# USB3_0_to_SATA.net
KiCad netlist of a schematic drawn in EAGLE
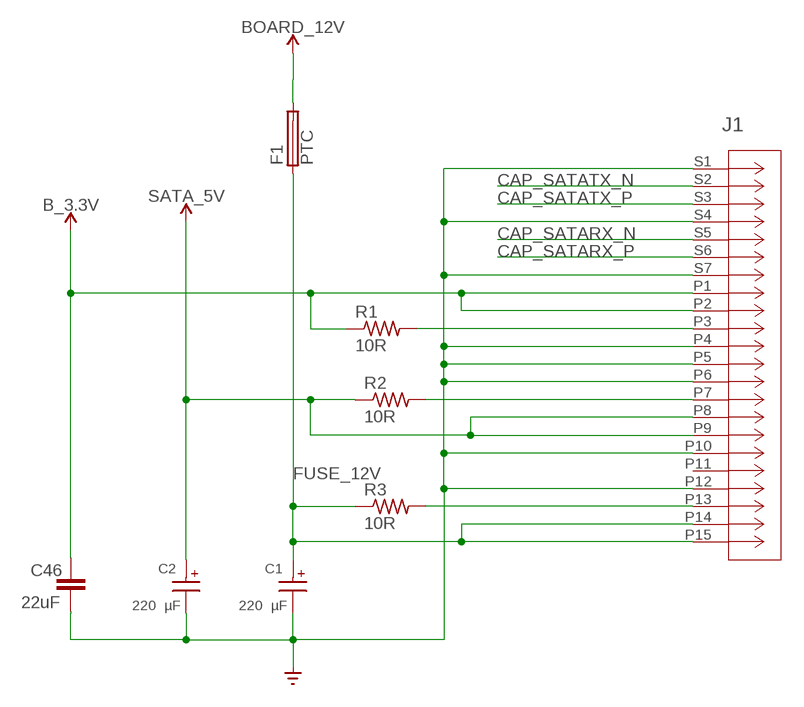
[diagram p0: schematic, sheet 1, part 1 of 2]
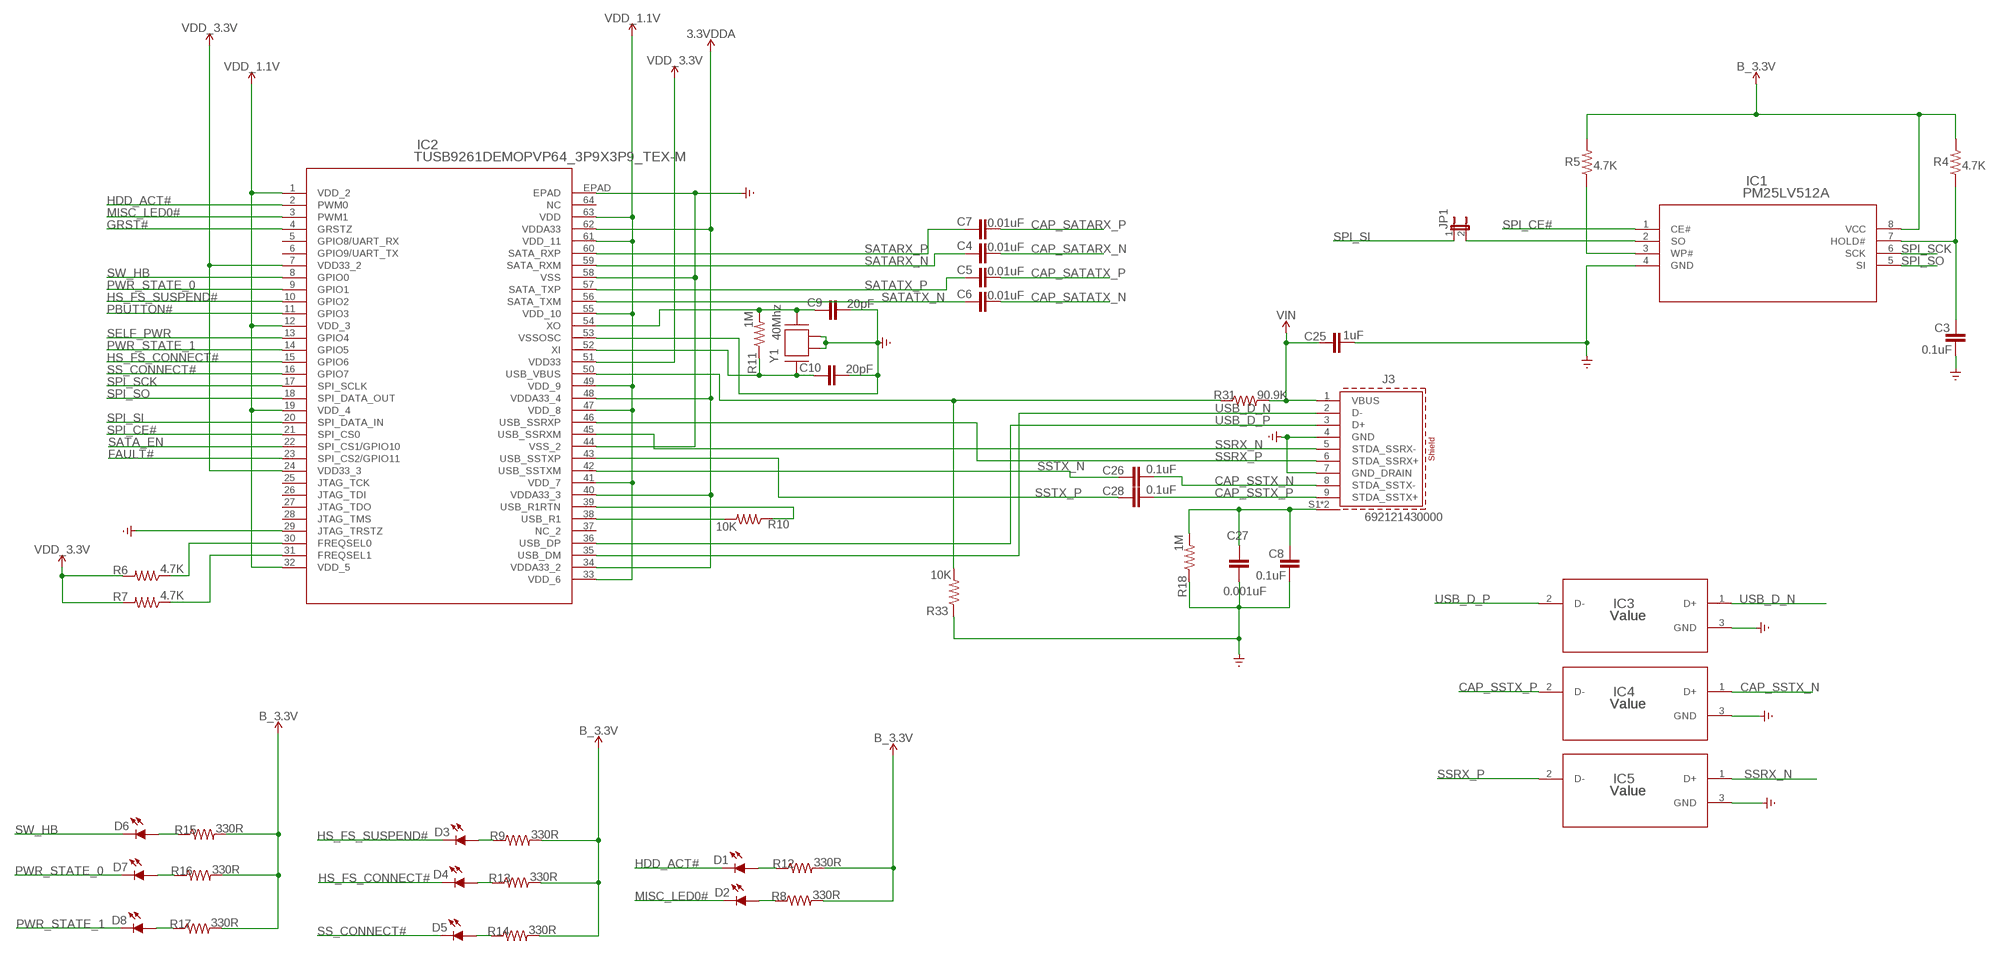
[diagram p1: schematic, sheet 1, part 2 of 2]
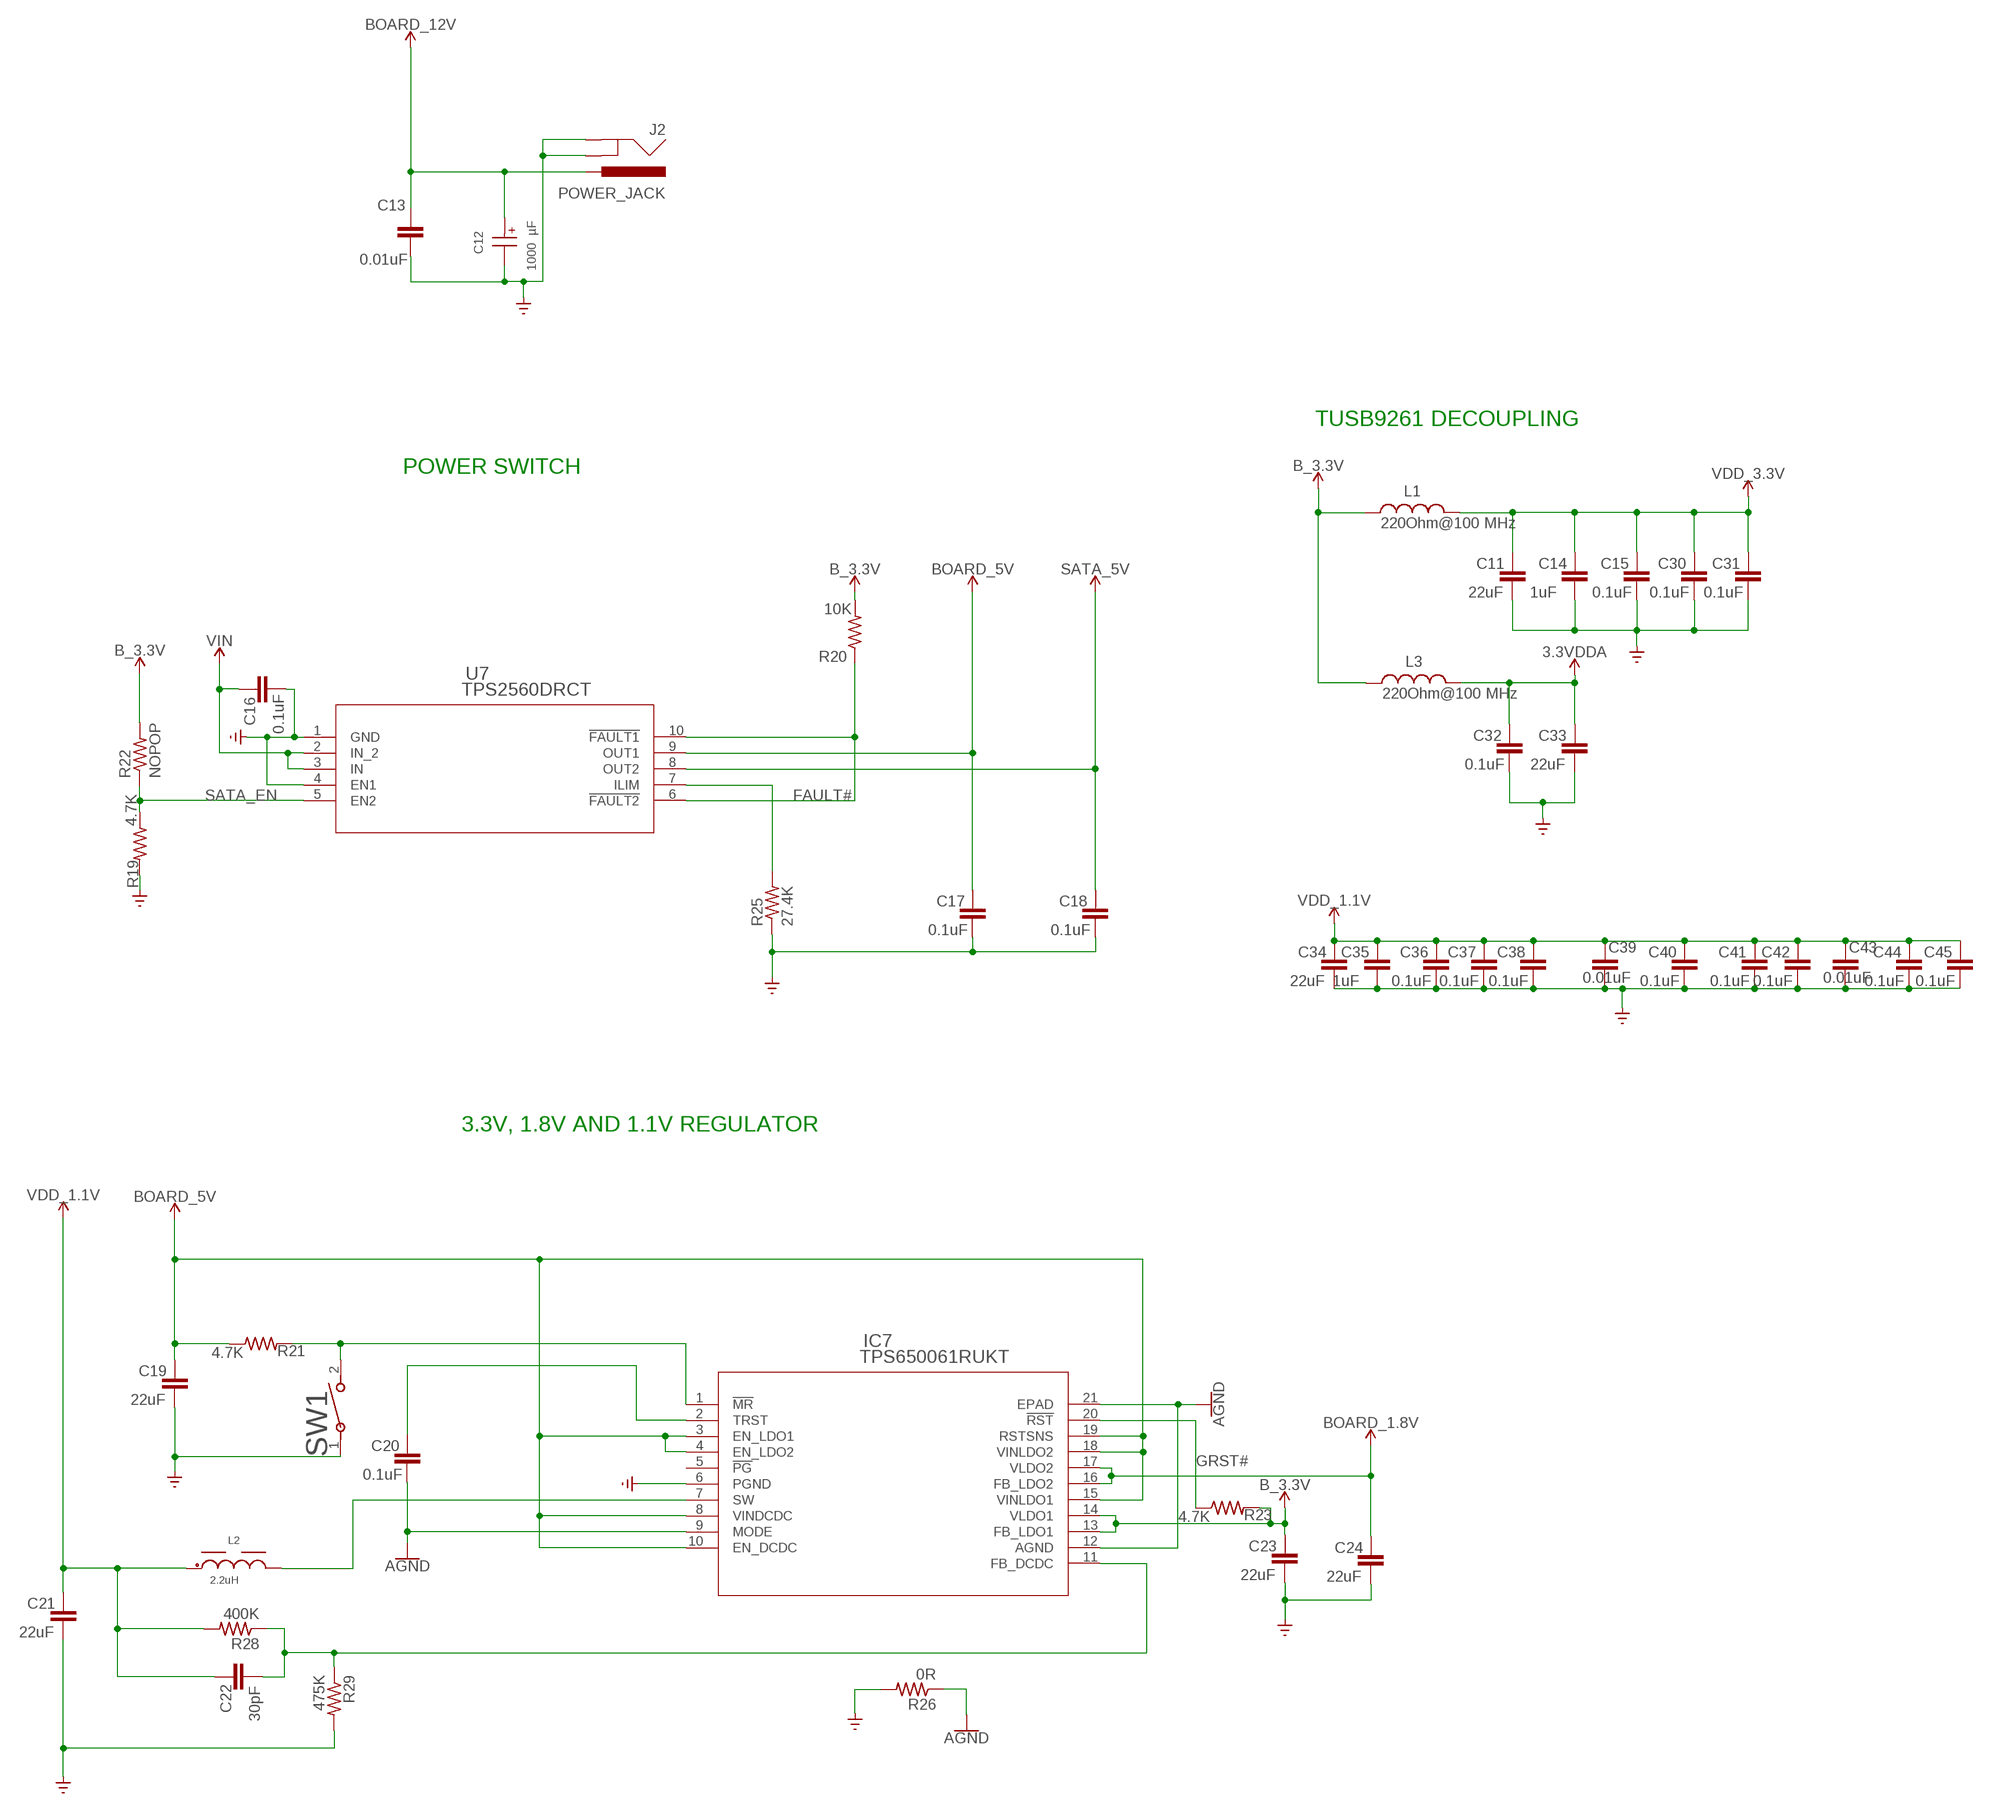
[diagram p2: schematic, sheet 2]

(export (version "E")
  (design (tool "Eeschema 10.0.6"))
  (components
    (comp (ref "C11")
      (value "22uF")
      (footprint "eagle-import:CAP_0402")
      (fields
        (field (name "DIGIKEY_PART_NUMBER") "311-2076-2-ND")
        (field (name "MANUFACTURER") "Yageo")
        (field (name "MPN") "CC0402CRNPO9BN1R0")
        (field (name "DIGIKEY_PART_NUMBER_1") "1276-7090-1-ND")
        (field (name "MANUFACTURER_1") "Samsung Electro-Mechanics")
        (field (name "MPN_1") "CL05A226MQ5N6J8")
        (field (name "CREATED_BY") "PCBLayout.com")
      )
      (libsource (lib "eagle-import") (part "CC0402CRNPO9BN1R0"))
    )
    (comp (ref "C12")
      (value "1000 µF")
      (footprint "eagle-import:WCAP-ATLL_10X16(DXL)")
      (fields (field (name "MPN") "860160375032"))
      (libsource (lib "eagle-import") (part "WCAP-ATLL_10X16_860160375032"))
    )
    (comp (ref "C13")
      (value "0.01uF")
      (footprint "eagle-import:CAP_0402")
      (fields
        (field (name "DIGIKEY_PART_NUMBER") "311-2076-2-ND")
        (field (name "MANUFACTURER") "Yageo")
        (field (name "MPN") "CC0402CRNPO9BN1R0")
        (field (name "DIGIKEY_PART_NUMBER_1") "490-6326-1-ND")
        (field (name "MANUFACTURER_1") "Murata Electronics")
        (field (name "MPN_1") "GRM155R71C103KA01J")
        (field (name "CREATED_BY") "PCBLayout.com")
      )
      (libsource (lib "eagle-import") (part "CC0402CRNPO9BN1R0"))
    )
    (comp (ref "C14")
      (value "1uF")
      (footprint "eagle-import:CAP_0402")
      (fields
        (field (name "DIGIKEY_PART_NUMBER") "311-2076-2-ND")
        (field (name "MANUFACTURER") "Yageo")
        (field (name "MPN") "CC0402CRNPO9BN1R0")
        (field (name "DIGIKEY_PART_NUMBER_1") "311-1691-1-ND")
        (field (name "MPN_1") "CC0402KRX5R7BB105")
        (field (name "CREATED_BY") "PCBLayout.com")
      )
      (libsource (lib "eagle-import") (part "CC0402CRNPO9BN1R0"))
    )
    (comp (ref "C15")
      (value "0.1uF")
      (footprint "eagle-import:CAP_0402")
      (fields
        (field (name "DIGIKEY_PART_NUMBER") "311-2076-2-ND")
        (field (name "MANUFACTURER") "Yageo")
        (field (name "MPN") "CC0402CRNPO9BN1R0")
        (field (name "DIGIKEY_PART_NUMBER_1") "311-3559-1-ND")
        (field (name "MPN_1") "CC0402KPX7R7BB104")
        (field (name "CREATED_BY") "PCBLayout.com")
      )
      (libsource (lib "eagle-import") (part "CC0402CRNPO9BN1R0"))
    )
    (comp (ref "C16")
      (value "0.1uF")
      (footprint "eagle-import:CAP_0402")
      (fields
        (field (name "DIGIKEY_PART_NUMBER") "311-2076-2-ND")
        (field (name "MANUFACTURER") "Yageo")
        (field (name "MPN") "CC0402CRNPO9BN1R0")
        (field (name "DIGIKEY_PART_NUMBER_1") "311-3559-1-ND")
        (field (name "MPN_1") "CC0402KPX7R7BB104")
        (field (name "CREATED_BY") "PCBLayout.com")
      )
      (libsource (lib "eagle-import") (part "CC0402CRNPO9BN1R0"))
    )
    (comp (ref "C17")
      (value "0.1uF")
      (footprint "eagle-import:CAP_0402")
      (fields
        (field (name "DIGIKEY_PART_NUMBER") "311-2076-2-ND")
        (field (name "MANUFACTURER") "Yageo")
        (field (name "MPN") "CC0402CRNPO9BN1R0")
        (field (name "DIGIKEY_PART_NUMBER_1") "311-3559-1-ND")
        (field (name "MPN_1") "CC0402KPX7R7BB104")
        (field (name "CREATED_BY") "PCBLayout.com")
      )
      (libsource (lib "eagle-import") (part "CC0402CRNPO9BN1R0"))
    )
    (comp (ref "C18")
      (value "0.1uF")
      (footprint "eagle-import:CAP_0402")
      (fields
        (field (name "DIGIKEY_PART_NUMBER") "311-2076-2-ND")
        (field (name "MANUFACTURER") "Yageo")
        (field (name "MPN") "CC0402CRNPO9BN1R0")
        (field (name "DIGIKEY_PART_NUMBER_1") "311-3559-1-ND")
        (field (name "MPN_1") "CC0402KPX7R7BB104")
        (field (name "CREATED_BY") "PCBLayout.com")
      )
      (libsource (lib "eagle-import") (part "CC0402CRNPO9BN1R0"))
    )
    (comp (ref "C19")
      (value "22uF")
      (footprint "eagle-import:CAP_0402")
      (fields
        (field (name "DIGIKEY_PART_NUMBER") "311-2076-2-ND")
        (field (name "MANUFACTURER") "Yageo")
        (field (name "MPN") "CC0402CRNPO9BN1R0")
        (field (name "DIGIKEY_PART_NUMBER_1") "1276-7090-1-ND")
        (field (name "MANUFACTURER_1") "Samsung Electro-Mechanics")
        (field (name "MPN_1") "CL05A226MQ5N6J8")
        (field (name "CREATED_BY") "PCBLayout.com")
      )
      (libsource (lib "eagle-import") (part "CC0402CRNPO9BN1R0"))
    )
    (comp (ref "C20")
      (value "0.1uF")
      (footprint "eagle-import:CAP_0402")
      (fields
        (field (name "DIGIKEY_PART_NUMBER") "311-2076-2-ND")
        (field (name "MANUFACTURER") "Yageo")
        (field (name "MPN") "CC0402CRNPO9BN1R0")
        (field (name "DIGIKEY_PART_NUMBER_1") "311-3559-1-ND")
        (field (name "MPN_1") "CC0402KPX7R7BB104")
        (field (name "CREATED_BY") "PCBLayout.com")
      )
      (libsource (lib "eagle-import") (part "CC0402CRNPO9BN1R0"))
    )
    (comp (ref "C21")
      (value "22uF")
      (footprint "eagle-import:CAP_0402")
      (fields
        (field (name "DIGIKEY_PART_NUMBER") "311-2076-2-ND")
        (field (name "MANUFACTURER") "Yageo")
        (field (name "MPN") "CC0402CRNPO9BN1R0")
        (field (name "DIGIKEY_PART_NUMBER_1") "1276-7090-1-ND")
        (field (name "MANUFACTURER_1") "Samsung Electro-Mechanics")
        (field (name "MPN_1") "CL05A226MQ5N6J8")
        (field (name "CREATED_BY") "PCBLayout.com")
      )
      (libsource (lib "eagle-import") (part "CC0402CRNPO9BN1R0"))
    )
    (comp (ref "C22")
      (value "30pF")
      (footprint "eagle-import:CAP_0402")
      (fields
        (field (name "DIGIKEY_PART_NUMBER") "311-2076-2-ND")
        (field (name "MANUFACTURER") "Yageo")
        (field (name "MPN") "CC0402CRNPO9BN1R0")
        (field (name "DIGIKEY_PART_NUMBER_1") "490-7752-1-ND")
        (field (name "MANUFACTURER_1") "Murata Electronics")
        (field (name "MPN_1") "GRM1555C1E300JA01D")
        (field (name "CREATED_BY") "PCBLayout.com")
      )
      (libsource (lib "eagle-import") (part "CC0402CRNPO9BN1R0"))
    )
    (comp (ref "C23")
      (value "22uF")
      (footprint "eagle-import:CAP_0402")
      (fields
        (field (name "DIGIKEY_PART_NUMBER") "311-2076-2-ND")
        (field (name "MANUFACTURER") "Yageo")
        (field (name "MPN") "CC0402CRNPO9BN1R0")
        (field (name "DIGIKEY_PART_NUMBER_1") "1276-7090-1-ND")
        (field (name "MANUFACTURER_1") "Samsung Electro-Mechanics")
        (field (name "MPN_1") "CL05A226MQ5N6J8")
        (field (name "CREATED_BY") "PCBLayout.com")
      )
      (libsource (lib "eagle-import") (part "CC0402CRNPO9BN1R0"))
    )
    (comp (ref "C24")
      (value "22uF")
      (footprint "eagle-import:CAP_0402")
      (fields
        (field (name "DIGIKEY_PART_NUMBER") "311-2076-2-ND")
        (field (name "MANUFACTURER") "Yageo")
        (field (name "MPN") "CC0402CRNPO9BN1R0")
        (field (name "DIGIKEY_PART_NUMBER_1") "1276-7090-1-ND")
        (field (name "MANUFACTURER_1") "Samsung Electro-Mechanics")
        (field (name "MPN_1") "CL05A226MQ5N6J8")
        (field (name "CREATED_BY") "PCBLayout.com")
      )
      (libsource (lib "eagle-import") (part "CC0402CRNPO9BN1R0"))
    )
    (comp (ref "C30")
      (value "0.1uF")
      (footprint "eagle-import:CAP_0402")
      (fields
        (field (name "DIGIKEY_PART_NUMBER") "311-2076-2-ND")
        (field (name "MANUFACTURER") "Yageo")
        (field (name "MPN") "CC0402CRNPO9BN1R0")
        (field (name "DIGIKEY_PART_NUMBER_1") "311-3559-1-ND")
        (field (name "MPN_1") "CC0402KPX7R7BB104")
        (field (name "CREATED_BY") "PCBLayout.com")
      )
      (libsource (lib "eagle-import") (part "CC0402CRNPO9BN1R0"))
    )
    (comp (ref "C31")
      (value "0.1uF")
      (footprint "eagle-import:CAP_0402")
      (fields
        (field (name "DIGIKEY_PART_NUMBER") "311-2076-2-ND")
        (field (name "MANUFACTURER") "Yageo")
        (field (name "MPN") "CC0402CRNPO9BN1R0")
        (field (name "DIGIKEY_PART_NUMBER_1") "311-3559-1-ND")
        (field (name "MPN_1") "CC0402KPX7R7BB104")
        (field (name "CREATED_BY") "PCBLayout.com")
      )
      (libsource (lib "eagle-import") (part "CC0402CRNPO9BN1R0"))
    )
    (comp (ref "C32")
      (value "0.1uF")
      (footprint "eagle-import:CAP_0402")
      (fields
        (field (name "DIGIKEY_PART_NUMBER") "311-2076-2-ND")
        (field (name "MANUFACTURER") "Yageo")
        (field (name "MPN") "CC0402CRNPO9BN1R0")
        (field (name "DIGIKEY_PART_NUMBER_1") "311-3559-1-ND")
        (field (name "MPN_1") "CC0402KPX7R7BB104")
        (field (name "CREATED_BY") "PCBLayout.com")
      )
      (libsource (lib "eagle-import") (part "CC0402CRNPO9BN1R0"))
    )
    (comp (ref "C33")
      (value "22uF")
      (footprint "eagle-import:CAP_0402")
      (fields
        (field (name "DIGIKEY_PART_NUMBER") "311-2076-2-ND")
        (field (name "MANUFACTURER") "Yageo")
        (field (name "MPN") "CC0402CRNPO9BN1R0")
        (field (name "DIGIKEY_PART_NUMBER_1") "1276-7090-1-ND")
        (field (name "MANUFACTURER_1") "Samsung Electro-Mechanics")
        (field (name "MPN_1") "CL05A226MQ5N6J8")
        (field (name "CREATED_BY") "PCBLayout.com")
      )
      (libsource (lib "eagle-import") (part "CC0402CRNPO9BN1R0"))
    )
    (comp (ref "C34")
      (value "22uF")
      (footprint "eagle-import:CAP_0402")
      (fields
        (field (name "DIGIKEY_PART_NUMBER") "311-2076-2-ND")
        (field (name "MANUFACTURER") "Yageo")
        (field (name "MPN") "CC0402CRNPO9BN1R0")
        (field (name "DIGIKEY_PART_NUMBER_1") "1276-7090-1-ND")
        (field (name "MANUFACTURER_1") "Samsung Electro-Mechanics")
        (field (name "MPN_1") "CL05A226MQ5N6J8")
        (field (name "CREATED_BY") "PCBLayout.com")
      )
      (libsource (lib "eagle-import") (part "CC0402CRNPO9BN1R0"))
    )
    (comp (ref "C35")
      (value "1uF")
      (footprint "eagle-import:CAP_0402")
      (fields
        (field (name "DIGIKEY_PART_NUMBER") "311-2076-2-ND")
        (field (name "MANUFACTURER") "Yageo")
        (field (name "MPN") "CC0402CRNPO9BN1R0")
        (field (name "DIGIKEY_PART_NUMBER_1") "311-1691-1-ND")
        (field (name "MPN_1") "CC0402KRX5R7BB105")
        (field (name "CREATED_BY") "PCBLayout.com")
      )
      (libsource (lib "eagle-import") (part "CC0402CRNPO9BN1R0"))
    )
    (comp (ref "C36")
      (value "0.1uF")
      (footprint "eagle-import:CAP_0402")
      (fields
        (field (name "DIGIKEY_PART_NUMBER") "311-2076-2-ND")
        (field (name "MANUFACTURER") "Yageo")
        (field (name "MPN") "CC0402CRNPO9BN1R0")
        (field (name "DIGIKEY_PART_NUMBER_1") "311-3559-1-ND")
        (field (name "MPN_1") "CC0402KPX7R7BB104")
        (field (name "CREATED_BY") "PCBLayout.com")
      )
      (libsource (lib "eagle-import") (part "CC0402CRNPO9BN1R0"))
    )
    (comp (ref "C37")
      (value "0.1uF")
      (footprint "eagle-import:CAP_0402")
      (fields
        (field (name "DIGIKEY_PART_NUMBER") "311-2076-2-ND")
        (field (name "MANUFACTURER") "Yageo")
        (field (name "MPN") "CC0402CRNPO9BN1R0")
        (field (name "DIGIKEY_PART_NUMBER_1") "311-3559-1-ND")
        (field (name "MPN_1") "CC0402KPX7R7BB104")
        (field (name "CREATED_BY") "PCBLayout.com")
      )
      (libsource (lib "eagle-import") (part "CC0402CRNPO9BN1R0"))
    )
    (comp (ref "C38")
      (value "0.1uF")
      (footprint "eagle-import:CAP_0402")
      (fields
        (field (name "DIGIKEY_PART_NUMBER") "311-2076-2-ND")
        (field (name "MANUFACTURER") "Yageo")
        (field (name "MPN") "CC0402CRNPO9BN1R0")
        (field (name "DIGIKEY_PART_NUMBER_1") "311-3559-1-ND")
        (field (name "MPN_1") "CC0402KPX7R7BB104")
        (field (name "CREATED_BY") "PCBLayout.com")
      )
      (libsource (lib "eagle-import") (part "CC0402CRNPO9BN1R0"))
    )
    (comp (ref "C39")
      (value "0.01uF")
      (footprint "eagle-import:CAP_0402")
      (fields
        (field (name "DIGIKEY_PART_NUMBER") "311-2076-2-ND")
        (field (name "MANUFACTURER") "Yageo")
        (field (name "MPN") "CC0402CRNPO9BN1R0")
        (field (name "DIGIKEY_PART_NUMBER_1") "490-6326-1-ND")
        (field (name "MANUFACTURER_1") "Murata Electronics")
        (field (name "MPN_1") "GRM155R71C103KA01J")
        (field (name "CREATED_BY") "PCBLayout.com")
      )
      (libsource (lib "eagle-import") (part "CC0402CRNPO9BN1R0"))
    )
    (comp (ref "C40")
      (value "0.1uF")
      (footprint "eagle-import:CAP_0402")
      (fields
        (field (name "DIGIKEY_PART_NUMBER") "311-2076-2-ND")
        (field (name "MANUFACTURER") "Yageo")
        (field (name "MPN") "CC0402CRNPO9BN1R0")
        (field (name "DIGIKEY_PART_NUMBER_1") "311-3559-1-ND")
        (field (name "MPN_1") "CC0402KPX7R7BB104")
        (field (name "CREATED_BY") "PCBLayout.com")
      )
      (libsource (lib "eagle-import") (part "CC0402CRNPO9BN1R0"))
    )
    (comp (ref "C41")
      (value "0.1uF")
      (footprint "eagle-import:CAP_0402")
      (fields
        (field (name "DIGIKEY_PART_NUMBER") "311-2076-2-ND")
        (field (name "MANUFACTURER") "Yageo")
        (field (name "MPN") "CC0402CRNPO9BN1R0")
        (field (name "DIGIKEY_PART_NUMBER_1") "311-3559-1-ND")
        (field (name "MPN_1") "CC0402KPX7R7BB104")
        (field (name "CREATED_BY") "PCBLayout.com")
      )
      (libsource (lib "eagle-import") (part "CC0402CRNPO9BN1R0"))
    )
    (comp (ref "C42")
      (value "0.1uF")
      (footprint "eagle-import:CAP_0402")
      (fields
        (field (name "DIGIKEY_PART_NUMBER") "311-2076-2-ND")
        (field (name "MANUFACTURER") "Yageo")
        (field (name "MPN") "CC0402CRNPO9BN1R0")
        (field (name "DIGIKEY_PART_NUMBER_1") "311-3559-1-ND")
        (field (name "MPN_1") "CC0402KPX7R7BB104")
        (field (name "CREATED_BY") "PCBLayout.com")
      )
      (libsource (lib "eagle-import") (part "CC0402CRNPO9BN1R0"))
    )
    (comp (ref "C43")
      (value "0.01uF")
      (footprint "eagle-import:CAP_0402")
      (fields
        (field (name "DIGIKEY_PART_NUMBER") "311-2076-2-ND")
        (field (name "MANUFACTURER") "Yageo")
        (field (name "MPN") "CC0402CRNPO9BN1R0")
        (field (name "DIGIKEY_PART_NUMBER_1") "490-6326-1-ND")
        (field (name "MANUFACTURER_1") "Murata Electronics")
        (field (name "MPN_1") "GRM155R71C103KA01J")
        (field (name "CREATED_BY") "PCBLayout.com")
      )
      (libsource (lib "eagle-import") (part "CC0402CRNPO9BN1R0"))
    )
    (comp (ref "C44")
      (value "0.1uF")
      (footprint "eagle-import:CAP_0402")
      (fields
        (field (name "DIGIKEY_PART_NUMBER") "311-2076-2-ND")
        (field (name "MANUFACTURER") "Yageo")
        (field (name "MPN") "CC0402CRNPO9BN1R0")
        (field (name "DIGIKEY_PART_NUMBER_1") "311-3559-1-ND")
        (field (name "MPN_1") "CC0402KPX7R7BB104")
        (field (name "CREATED_BY") "PCBLayout.com")
      )
      (libsource (lib "eagle-import") (part "CC0402CRNPO9BN1R0"))
    )
    (comp (ref "C45")
      (value "0.1uF")
      (footprint "eagle-import:CAP_0402")
      (fields
        (field (name "DIGIKEY_PART_NUMBER") "311-2076-2-ND")
        (field (name "MANUFACTURER") "Yageo")
        (field (name "MPN") "CC0402CRNPO9BN1R0")
        (field (name "DIGIKEY_PART_NUMBER_1") "311-3559-1-ND")
        (field (name "MPN_1") "CC0402KPX7R7BB104")
        (field (name "CREATED_BY") "PCBLayout.com")
      )
      (libsource (lib "eagle-import") (part "CC0402CRNPO9BN1R0"))
    )
    (comp (ref "IC7")
      (value "TPS650061RUKT")
      (footprint "eagle-import:RUK20_1P7X1P7")
      (fields
        (field (name "GENERIC_PART_NUMBER") "TPS650061")
        (field (name "MANUFACTURER") "Texas Instruments")
      )
      (libsource (lib "eagle-import") (part "TPS650061RUKT"))
    )
    (comp (ref "J2")
      (value "POWER_JACK")
      (footprint "eagle-import:POWER_JACK_PTH")
      (libsource (lib "eagle-import") (part "POWER_JACK"))
    )
    (comp (ref "L1")
      (value "220Ohm@100 MHz")
      (footprint "eagle-import:WE-CBF_0603(W=2.2)")
      (fields (field (name "MPN") "74279263"))
      (libsource (lib "eagle-import") (part "WE-CBF_0603_WB_HS_74279263"))
    )
    (comp (ref "L2")
      (value "2.2uH")
      (footprint "eagle-import:WE-MAPI_4020")
      (libsource (lib "eagle-import") (part "WE-MAPI_4020_74438356022"))
    )
    (comp (ref "L3")
      (value "220Ohm@100 MHz")
      (footprint "eagle-import:WE-CBF_0603(W=2.2)")
      (fields (field (name "MPN") "74279263"))
      (libsource (lib "eagle-import") (part "WE-CBF_0603_WB_HS_74279263"))
    )
    (comp (ref "R19")
      (value "4.7K")
      (footprint "eagle-import:RES_0402")
      (fields
        (field (name "DIGIKEY_PART_NUMBER") "311-0.0JRTR-ND")
        (field (name "MANUFACTURER") "Yageo")
        (field (name "MPN") "RC0402JR-070RL")
        (field (name "DIGIKEY_PART_NUMBER_1") "YAG1446CT-ND")
        (field (name "MPN_1") "RT0402BRD074K7L")
        (field (name "CREATED_BY") "PCBLayout.com")
      )
      (libsource (lib "eagle-import") (part "RC0402JR-070RL"))
    )
    (comp (ref "R20")
      (value "10K")
      (footprint "eagle-import:RES_0402")
      (fields
        (field (name "DIGIKEY_PART_NUMBER") "311-0.0JRTR-ND")
        (field (name "MANUFACTURER") "Yageo")
        (field (name "MPN") "RC0402JR-070RL")
        (field (name "DIGIKEY_PART_NUMBER_1") "541-1752-1-ND")
        (field (name "MANUFACTURER_1") "Vishay Dale")
        (field (name "MPN_1") "RCG04021M00FKED")
        (field (name "CREATED_BY") "PCBLayout.com")
      )
      (libsource (lib "eagle-import") (part "RC0402JR-070RL"))
    )
    (comp (ref "R21")
      (value "4.7K")
      (footprint "eagle-import:RES_0402")
      (fields
        (field (name "DIGIKEY_PART_NUMBER") "311-0.0JRTR-ND")
        (field (name "MANUFACTURER") "Yageo")
        (field (name "MPN") "RC0402JR-070RL")
        (field (name "DIGIKEY_PART_NUMBER_1") "YAG1446CT-ND")
        (field (name "MPN_1") "RT0402BRD074K7L")
        (field (name "CREATED_BY") "PCBLayout.com")
      )
      (libsource (lib "eagle-import") (part "RC0402JR-070RL"))
    )
    (comp (ref "R22")
      (value "NOPOP")
      (footprint "eagle-import:RES_0402")
      (fields
        (field (name "DIGIKEY_PART_NUMBER") "311-0.0JRTR-ND")
        (field (name "MANUFACTURER") "Yageo")
        (field (name "MPN") "RC0402JR-070RL")
        (field (name "CREATED_BY") "PCBLayout.com")
      )
      (libsource (lib "eagle-import") (part "RC0402JR-070RL"))
    )
    (comp (ref "R23")
      (value "4.7K")
      (footprint "eagle-import:RES_0402")
      (fields
        (field (name "DIGIKEY_PART_NUMBER") "311-0.0JRTR-ND")
        (field (name "MANUFACTURER") "Yageo")
        (field (name "MPN") "RC0402JR-070RL")
        (field (name "DIGIKEY_PART_NUMBER_1") "YAG1446CT-ND")
        (field (name "MPN_1") "RT0402BRD074K7L")
        (field (name "CREATED_BY") "PCBLayout.com")
      )
      (libsource (lib "eagle-import") (part "RC0402JR-070RL"))
    )
    (comp (ref "R25")
      (value "27.4K")
      (footprint "eagle-import:RES_0402")
      (fields
        (field (name "DIGIKEY_PART_NUMBER") "311-0.0JRTR-ND")
        (field (name "MANUFACTURER") "Yageo")
        (field (name "MPN") "RC0402JR-070RL")
        (field (name "DIGIKEY_PART_NUMBER_1") "YAG4427CT-ND")
        (field (name "MPN_1") "RT0402DRD0727K4L")
        (field (name "CREATED_BY") "PCBLayout.com")
      )
      (libsource (lib "eagle-import") (part "RC0402JR-070RL"))
    )
    (comp (ref "R26")
      (value "0R")
      (footprint "eagle-import:RES_0402")
      (fields
        (field (name "DIGIKEY_PART_NUMBER") "311-0.0JRTR-ND")
        (field (name "MANUFACTURER") "Yageo")
        (field (name "MPN") "RC0402JR-070RL")
        (field (name "DIGIKEY_PART_NUMBER_1") "13-AC0402FR-070RLCT-ND")
        (field (name "MPN_1") "AC0402FR-070RL")
        (field (name "CREATED_BY") "PCBLayout.com")
      )
      (libsource (lib "eagle-import") (part "RC0402JR-070RL"))
    )
    (comp (ref "R28")
      (value "400K")
      (footprint "eagle-import:RES_0402")
      (fields
        (field (name "DIGIKEY_PART_NUMBER") "311-0.0JRTR-ND")
        (field (name "MANUFACTURER") "Yageo")
        (field (name "MPN") "RC0402JR-070RL")
        (field (name "DIGIKEY_PART_NUMBER_1") "2997-CR204003FTR-ND")
        (field (name "MANUFACTURER_1") "Meritek")
        (field (name "MPN_1") "CR204003F")
        (field (name "CREATED_BY") "PCBLayout.com")
      )
      (libsource (lib "eagle-import") (part "RC0402JR-070RL"))
    )
    (comp (ref "R29")
      (value "475K")
      (footprint "eagle-import:RES_0402")
      (fields
        (field (name "DIGIKEY_PART_NUMBER") "311-0.0JRTR-ND")
        (field (name "MANUFACTURER") "Yageo")
        (field (name "MPN") "RC0402JR-070RL")
        (field (name "DIGIKEY_PART_NUMBER_1") "311-475KLRCT-ND")
        (field (name "MPN_1") "RC0402FR-07475KL")
        (field (name "CREATED_BY") "PCBLayout.com")
      )
      (libsource (lib "eagle-import") (part "RC0402JR-070RL"))
    )
    (comp (ref "SW1")
      (value "EVP-AWED2A")
      (footprint "eagle-import:SW_EVP-AWED2A_PAN")
      (fields (field (name "COPYRIGHT") "Copyright (C) 2018 Accelerated Designs. All rights reserved"))
      (libsource (lib "eagle-import") (part "EVP-AWED2A"))
    )
    (comp (ref "U7")
      (value "TPS2560DRCT")
      (footprint "eagle-import:DRC10_2P4X1P65")
      (fields
        (field (name "GENERIC_PART_NUMBER") "TPS2560")
        (field (name "MANUFACTURER") "Texas Instruments")
      )
      (libsource (lib "eagle-import") (part "TPS2560DRCT"))
    )
    (comp (ref "C1")
      (value "220 µF")
      (footprint "eagle-import:WCAP-ATUL_8X11.5(DXL)")
      (fields (field (name "MPN") " 860040374004 "))
      (libsource (lib "eagle-import") (part "WCAP-ATUL_8X11.5_860040374004"))
    )
    (comp (ref "C2")
      (value "220 µF")
      (footprint "eagle-import:WCAP-ATUL_8X11.5(DXL)")
      (fields (field (name "MPN") " 860040374004 "))
      (libsource (lib "eagle-import") (part "WCAP-ATUL_8X11.5_860040374004"))
    )
    (comp (ref "C3")
      (value "0.1uF")
      (footprint "eagle-import:CAP_0402")
      (fields
        (field (name "DIGIKEY_PART_NUMBER") "311-2076-2-ND")
        (field (name "MANUFACTURER") "Yageo")
        (field (name "MPN") "CC0402CRNPO9BN1R0")
        (field (name "DIGIKEY_PART_NUMBER_1") "311-3559-1-ND")
        (field (name "MPN_1") "CC0402KPX7R7BB104")
        (field (name "CREATED_BY") "PCBLayout.com")
      )
      (libsource (lib "eagle-import") (part "CC0402CRNPO9BN1R0"))
    )
    (comp (ref "C4")
      (value "0.01uF")
      (footprint "eagle-import:CAP_0402")
      (fields
        (field (name "DIGIKEY_PART_NUMBER") "311-2076-2-ND")
        (field (name "MANUFACTURER") "Yageo")
        (field (name "MPN") "CC0402CRNPO9BN1R0")
        (field (name "DIGIKEY_PART_NUMBER_1") "490-6326-1-ND")
        (field (name "MANUFACTURER_1") "Murata Electronics")
        (field (name "MPN_1") "GRM155R71C103KA01J")
        (field (name "CREATED_BY") "PCBLayout.com")
      )
      (libsource (lib "eagle-import") (part "CC0402CRNPO9BN1R0"))
    )
    (comp (ref "C5")
      (value "0.01uF")
      (footprint "eagle-import:CAP_0402")
      (fields
        (field (name "DIGIKEY_PART_NUMBER") "311-2076-2-ND")
        (field (name "MANUFACTURER") "Yageo")
        (field (name "MPN") "CC0402CRNPO9BN1R0")
        (field (name "DIGIKEY_PART_NUMBER_1") "490-6326-1-ND")
        (field (name "MANUFACTURER_1") "Murata Electronics")
        (field (name "MPN_1") "GRM155R71C103KA01J")
        (field (name "CREATED_BY") "PCBLayout.com")
      )
      (libsource (lib "eagle-import") (part "CC0402CRNPO9BN1R0"))
    )
    (comp (ref "C6")
      (value "0.01uF")
      (footprint "eagle-import:CAP_0402")
      (fields
        (field (name "DIGIKEY_PART_NUMBER") "311-2076-2-ND")
        (field (name "MANUFACTURER") "Yageo")
        (field (name "MPN") "CC0402CRNPO9BN1R0")
        (field (name "DIGIKEY_PART_NUMBER_1") "490-6326-1-ND")
        (field (name "MANUFACTURER_1") "Murata Electronics")
        (field (name "MPN_1") "GRM155R71C103KA01J")
        (field (name "CREATED_BY") "PCBLayout.com")
      )
      (libsource (lib "eagle-import") (part "CC0402CRNPO9BN1R0"))
    )
    (comp (ref "C7")
      (value "0.01uF")
      (footprint "eagle-import:CAP_0402")
      (fields
        (field (name "DIGIKEY_PART_NUMBER") "311-2076-2-ND")
        (field (name "MANUFACTURER") "Yageo")
        (field (name "MPN") "CC0402CRNPO9BN1R0")
        (field (name "DIGIKEY_PART_NUMBER_1") "490-6326-1-ND")
        (field (name "MANUFACTURER_1") "Murata Electronics")
        (field (name "MPN_1") "GRM155R71C103KA01J")
        (field (name "CREATED_BY") "PCBLayout.com")
      )
      (libsource (lib "eagle-import") (part "CC0402CRNPO9BN1R0"))
    )
    (comp (ref "C8")
      (value "0.1uF")
      (footprint "eagle-import:CAP_0402")
      (fields
        (field (name "DIGIKEY_PART_NUMBER") "311-2076-2-ND")
        (field (name "MANUFACTURER") "Yageo")
        (field (name "MPN") "CC0402CRNPO9BN1R0")
        (field (name "DIGIKEY_PART_NUMBER_1") "311-3559-1-ND")
        (field (name "MPN_1") "CC0402KPX7R7BB104")
        (field (name "CREATED_BY") "PCBLayout.com")
      )
      (libsource (lib "eagle-import") (part "CC0402CRNPO9BN1R0"))
    )
    (comp (ref "C9")
      (value "20pF")
      (footprint "eagle-import:CAP_0402")
      (fields
        (field (name "DIGIKEY_PART_NUMBER") "311-2076-2-ND")
        (field (name "MANUFACTURER") "Yageo")
        (field (name "MPN") "CC0402CRNPO9BN1R0")
        (field (name "DIGIKEY_PART_NUMBER_1") "478-11758-1-ND")
        (field (name "MANUFACTURER_1") "AVX Corporation")
        (field (name "MPN_1") "04023U200JAT2A")
        (field (name "CREATED_BY") "PCBLayout.com")
      )
      (libsource (lib "eagle-import") (part "CC0402CRNPO9BN1R0"))
    )
    (comp (ref "C10")
      (value "20pF")
      (footprint "eagle-import:CAP_0402")
      (fields
        (field (name "DIGIKEY_PART_NUMBER") "311-2076-2-ND")
        (field (name "MANUFACTURER") "Yageo")
        (field (name "MPN") "CC0402CRNPO9BN1R0")
        (field (name "DIGIKEY_PART_NUMBER_1") "478-11758-1-ND")
        (field (name "MANUFACTURER_1") "AVX Corporation")
        (field (name "MPN_1") "04023U200JAT2A")
        (field (name "CREATED_BY") "PCBLayout.com")
      )
      (libsource (lib "eagle-import") (part "CC0402CRNPO9BN1R0"))
    )
    (comp (ref "C25")
      (value "1uF")
      (footprint "eagle-import:CAP_0402")
      (fields
        (field (name "DIGIKEY_PART_NUMBER") "311-2076-2-ND")
        (field (name "MANUFACTURER") "Yageo")
        (field (name "MPN") "CC0402CRNPO9BN1R0")
        (field (name "DIGIKEY_PART_NUMBER_1") "311-1691-1-ND")
        (field (name "MPN_1") "CC0402KRX5R7BB105")
        (field (name "CREATED_BY") "PCBLayout.com")
      )
      (libsource (lib "eagle-import") (part "CC0402CRNPO9BN1R0"))
    )
    (comp (ref "C26")
      (value "0.1uF")
      (footprint "eagle-import:CAP_0402")
      (fields
        (field (name "DIGIKEY_PART_NUMBER") "311-2076-2-ND")
        (field (name "MANUFACTURER") "Yageo")
        (field (name "MPN") "CC0402CRNPO9BN1R0")
        (field (name "DIGIKEY_PART_NUMBER_1") "311-3559-1-ND")
        (field (name "MPN_1") "CC0402KPX7R7BB104")
        (field (name "CREATED_BY") "PCBLayout.com")
      )
      (libsource (lib "eagle-import") (part "CC0402CRNPO9BN1R0"))
    )
    (comp (ref "C27")
      (value "0.001uF")
      (footprint "eagle-import:CAP_0402")
      (fields
        (field (name "DIGIKEY_PART_NUMBER") "311-2076-2-ND")
        (field (name "MANUFACTURER") "Yageo")
        (field (name "MPN") "CC0402CRNPO9BN1R0")
        (field (name "DIGIKEY_PART_NUMBER_1") "311-1712-1-ND")
        (field (name "MPN_1") "CC0402KRX7R8BB102")
        (field (name "CREATED_BY") "PCBLayout.com")
      )
      (libsource (lib "eagle-import") (part "CC0402CRNPO9BN1R0"))
    )
    (comp (ref "C28")
      (value "0.1uF")
      (footprint "eagle-import:CAP_0402")
      (fields
        (field (name "DIGIKEY_PART_NUMBER") "311-2076-2-ND")
        (field (name "MANUFACTURER") "Yageo")
        (field (name "MPN") "CC0402CRNPO9BN1R0")
        (field (name "DIGIKEY_PART_NUMBER_1") "311-3559-1-ND")
        (field (name "MPN_1") "CC0402KPX7R7BB104")
        (field (name "CREATED_BY") "PCBLayout.com")
      )
      (libsource (lib "eagle-import") (part "CC0402CRNPO9BN1R0"))
    )
    (comp (ref "C46")
      (value "22uF")
      (footprint "eagle-import:CAP_0402")
      (fields
        (field (name "DIGIKEY_PART_NUMBER") "311-2076-2-ND")
        (field (name "MANUFACTURER") "Yageo")
        (field (name "MPN") "CC0402CRNPO9BN1R0")
        (field (name "DIGIKEY_PART_NUMBER_1") "1276-7090-1-ND")
        (field (name "MANUFACTURER_1") "Samsung Electro-Mechanics")
        (field (name "MPN_1") "CL05A226MQ5N6J8")
        (field (name "CREATED_BY") "PCBLayout.com")
      )
      (libsource (lib "eagle-import") (part "CC0402CRNPO9BN1R0"))
    )
    (comp (ref "D1")
      (value "LED_LEDCHIP-LED0603MP")
      (footprint "eagle-import:LED_CHIP-LED0603MP")
      (fields (field (name "DIGIKEY_PART_NUMBER") "2460-L196L-SGC-TR-ND"))
      (libsource (lib "eagle-import") (part "LED_LEDCHIP-LED0603MP"))
    )
    (comp (ref "D2")
      (value "LED_LEDCHIP-LED0603MP")
      (footprint "eagle-import:LED_CHIP-LED0603MP")
      (fields (field (name "DIGIKEY_PART_NUMBER") "2460-L196L-SGC-TR-ND"))
      (libsource (lib "eagle-import") (part "LED_LEDCHIP-LED0603MP"))
    )
    (comp (ref "D3")
      (value "LED_LEDCHIP-LED0603MP")
      (footprint "eagle-import:LED_CHIP-LED0603MP")
      (fields (field (name "DIGIKEY_PART_NUMBER") "2460-L196L-SGC-TR-ND"))
      (libsource (lib "eagle-import") (part "LED_LEDCHIP-LED0603MP"))
    )
    (comp (ref "D4")
      (value "LED_LEDCHIP-LED0603MP")
      (footprint "eagle-import:LED_CHIP-LED0603MP")
      (fields (field (name "DIGIKEY_PART_NUMBER") "2460-L196L-SGC-TR-ND"))
      (libsource (lib "eagle-import") (part "LED_LEDCHIP-LED0603MP"))
    )
    (comp (ref "D5")
      (value "LED_LEDCHIP-LED0603MP")
      (footprint "eagle-import:LED_CHIP-LED0603MP")
      (fields (field (name "DIGIKEY_PART_NUMBER") "2460-L196L-SGC-TR-ND"))
      (libsource (lib "eagle-import") (part "LED_LEDCHIP-LED0603MP"))
    )
    (comp (ref "D6")
      (value "LED_LEDCHIP-LED0603MP")
      (footprint "eagle-import:LED_CHIP-LED0603MP")
      (fields (field (name "DIGIKEY_PART_NUMBER") "2460-L196L-SGC-TR-ND"))
      (libsource (lib "eagle-import") (part "LED_LEDCHIP-LED0603MP"))
    )
    (comp (ref "D7")
      (value "LED_LEDCHIP-LED0603MP")
      (footprint "eagle-import:LED_CHIP-LED0603MP")
      (fields (field (name "DIGIKEY_PART_NUMBER") "2460-L196L-SGC-TR-ND"))
      (libsource (lib "eagle-import") (part "LED_LEDCHIP-LED0603MP"))
    )
    (comp (ref "D8")
      (value "LED_LEDCHIP-LED0603MP")
      (footprint "eagle-import:LED_CHIP-LED0603MP")
      (fields (field (name "DIGIKEY_PART_NUMBER") "2460-L196L-SGC-TR-ND"))
      (libsource (lib "eagle-import") (part "LED_LEDCHIP-LED0603MP"))
    )
    (comp (ref "F1")
      (value "PTC")
      (footprint "eagle-import:FUSC3215X82N")
      (description "PTC RESET FUSE 21V 4A 1206")
      (fields
        (field (name "MANUFACTURER") "Littelfuse Inc.")
        (field (name "MPN") "NANOSMDC020F-2")
        (field (name "MPN_1") "400CC1206LR-C-2")
      )
      (libsource (lib "eagle-import") (part "FUSE__CHIP-1206NANOSMDC020F-2"))
    )
    (comp (ref "IC1")
      (value "PM25LV512A")
      (footprint "eagle-import:SOIC8-N_MC_MCH")
      (libsource (lib "eagle-import") (part "PM25LV512A"))
    )
    (comp (ref "IC2")
      (value "TUSB9261DEMOPVP64_3P9X3P9_TEX-M")
      (footprint "eagle-import:PVP64_3P9X3P9_TEX-M")
      (fields
        (field (name "MANUFACTURER_PART_NUMBER") "TUSB9261DEMO")
        (field (name "COPYRIGHT") "Copyright (C) 2018 Accelerated Designs. All rights reserved")
      )
      (libsource (lib "eagle-import") (part "TUSB9261DEMOPVP64_3P9X3P9_TEX-M"))
    )
    (comp (ref "IC3")
      (value "Value")
      (footprint "eagle-import:DRT0003A")
      (fields (field (name "MANUFACTURER") "Texas Instruments") (field (name "PARTNUMBER") "TPD2EUSB30DRTR"))
      (libsource (lib "eagle-import") (part "TPD2EUSB30DRTR"))
    )
    (comp (ref "IC4")
      (value "Value")
      (footprint "eagle-import:DRT0003A")
      (fields (field (name "MANUFACTURER") "Texas Instruments") (field (name "PARTNUMBER") "TPD2EUSB30DRTR"))
      (libsource (lib "eagle-import") (part "TPD2EUSB30DRTR"))
    )
    (comp (ref "IC5")
      (value "Value")
      (footprint "eagle-import:DRT0003A")
      (fields (field (name "MANUFACTURER") "Texas Instruments") (field (name "PARTNUMBER") "TPD2EUSB30DRTR"))
      (libsource (lib "eagle-import") (part "TPD2EUSB30DRTR"))
    )
    (comp (ref "J1")
      (value "10031569-001LF")
      (footprint "eagle-import:CONN_10031569-001LF_AMP")
      (fields (field (name "COPYRIGHT") "Copyright (C) 2018 Accelerated Designs. All rights reserved"))
      (libsource (lib "eagle-import") (part "10031569-001LF"))
    )
    (comp (ref "J3")
      (value "692121430000")
      (footprint "eagle-import:692121430000")
      (libsource (lib "eagle-import") (part "692121430000"))
    )
    (comp (ref "JP1")
      (value "JP1E")
      (footprint "eagle-import:JP1")
      (libsource (lib "eagle-import") (part "JP1E"))
    )
    (comp (ref "R1")
      (value "10R")
      (footprint "eagle-import:RES_0603")
      (fields
        (field (name "DIGIKEY_PART_NUMBER") "311-0.0GRTR-ND")
        (field (name "MANUFACTURER") "Yageo")
        (field (name "MPN") "RC0603JR-070RL")
        (field (name "DIGIKEY_PART_NUMBER_1") "511-1693-1-ND")
        (field (name "MANUFACTURER_1") "Rohm Semiconductor")
        (field (name "MPN_1") "SDR03EZPF10R0")
        (field (name "CREATED_BY") "PCBLayout.com")
      )
      (libsource (lib "eagle-import") (part "RC0603JR-070RL"))
    )
    (comp (ref "R2")
      (value "10R")
      (footprint "eagle-import:RES_0603")
      (fields
        (field (name "DIGIKEY_PART_NUMBER") "311-0.0GRTR-ND")
        (field (name "MANUFACTURER") "Yageo")
        (field (name "MPN") "RC0603JR-070RL")
        (field (name "DIGIKEY_PART_NUMBER_1") "511-1693-1-ND")
        (field (name "MANUFACTURER_1") "Rohm Semiconductor")
        (field (name "MPN_1") "SDR03EZPF10R0")
        (field (name "CREATED_BY") "PCBLayout.com")
      )
      (libsource (lib "eagle-import") (part "RC0603JR-070RL"))
    )
    (comp (ref "R3")
      (value "10R")
      (footprint "eagle-import:RES_0603")
      (fields
        (field (name "DIGIKEY_PART_NUMBER") "311-0.0GRTR-ND")
        (field (name "MANUFACTURER") "Yageo")
        (field (name "MPN") "RC0603JR-070RL")
        (field (name "DIGIKEY_PART_NUMBER_1") "511-1693-1-ND")
        (field (name "MANUFACTURER_1") "Rohm Semiconductor")
        (field (name "MPN_1") "SDR03EZPF10R0")
        (field (name "CREATED_BY") "PCBLayout.com")
      )
      (libsource (lib "eagle-import") (part "RC0603JR-070RL"))
    )
    (comp (ref "R4")
      (value "4.7K")
      (footprint "eagle-import:RES_0402")
      (fields
        (field (name "DIGIKEY_PART_NUMBER") "311-0.0JRTR-ND")
        (field (name "MANUFACTURER") "Yageo")
        (field (name "MPN") "RC0402JR-070RL")
        (field (name "DIGIKEY_PART_NUMBER_1") "YAG1446CT-ND")
        (field (name "MPN_1") "RT0402BRD074K7L")
        (field (name "CREATED_BY") "PCBLayout.com")
      )
      (libsource (lib "eagle-import") (part "RC0402JR-070RL"))
    )
    (comp (ref "R5")
      (value "4.7K")
      (footprint "eagle-import:RES_0402")
      (fields
        (field (name "DIGIKEY_PART_NUMBER") "311-0.0JRTR-ND")
        (field (name "MANUFACTURER") "Yageo")
        (field (name "MPN") "RC0402JR-070RL")
        (field (name "DIGIKEY_PART_NUMBER_1") "YAG1446CT-ND")
        (field (name "MPN_1") "RT0402BRD074K7L")
        (field (name "CREATED_BY") "PCBLayout.com")
      )
      (libsource (lib "eagle-import") (part "RC0402JR-070RL"))
    )
    (comp (ref "R6")
      (value "4.7K")
      (footprint "eagle-import:RES_0402")
      (fields
        (field (name "DIGIKEY_PART_NUMBER") "311-0.0JRTR-ND")
        (field (name "MANUFACTURER") "Yageo")
        (field (name "MPN") "RC0402JR-070RL")
        (field (name "DIGIKEY_PART_NUMBER_1") "YAG1446CT-ND")
        (field (name "MPN_1") "RT0402BRD074K7L")
        (field (name "CREATED_BY") "PCBLayout.com")
      )
      (libsource (lib "eagle-import") (part "RC0402JR-070RL"))
    )
    (comp (ref "R7")
      (value "4.7K")
      (footprint "eagle-import:RES_0402")
      (fields
        (field (name "DIGIKEY_PART_NUMBER") "311-0.0JRTR-ND")
        (field (name "MANUFACTURER") "Yageo")
        (field (name "MPN") "RC0402JR-070RL")
        (field (name "DIGIKEY_PART_NUMBER_1") "YAG1446CT-ND")
        (field (name "MPN_1") "RT0402BRD074K7L")
        (field (name "CREATED_BY") "PCBLayout.com")
      )
      (libsource (lib "eagle-import") (part "RC0402JR-070RL"))
    )
    (comp (ref "R8")
      (value "330R")
      (footprint "eagle-import:RES_0603")
      (fields
        (field (name "DIGIKEY_PART_NUMBER") "311-0.0GRTR-ND")
        (field (name "MANUFACTURER") "Yageo")
        (field (name "MPN") "RC0603JR-070RL")
        (field (name "DIGIKEY_PART_NUMBER_1") "511-1764-1-ND")
        (field (name "MANUFACTURER_1") "Rohm Semiconductor")
        (field (name "MPN_1") "SDR03EZPJ331")
        (field (name "CREATED_BY") "PCBLayout.com")
      )
      (libsource (lib "eagle-import") (part "RC0603JR-070RL"))
    )
    (comp (ref "R9")
      (value "330R")
      (footprint "eagle-import:RES_0603")
      (fields
        (field (name "DIGIKEY_PART_NUMBER") "311-0.0GRTR-ND")
        (field (name "MANUFACTURER") "Yageo")
        (field (name "MPN") "RC0603JR-070RL")
        (field (name "DIGIKEY_PART_NUMBER_1") "511-1764-1-ND")
        (field (name "MANUFACTURER_1") "Rohm Semiconductor")
        (field (name "MPN_1") "SDR03EZPJ331")
        (field (name "CREATED_BY") "PCBLayout.com")
      )
      (libsource (lib "eagle-import") (part "RC0603JR-070RL"))
    )
    (comp (ref "R10")
      (value "10K")
      (footprint "eagle-import:RES_0402")
      (fields
        (field (name "DIGIKEY_PART_NUMBER") "311-0.0JRTR-ND")
        (field (name "MANUFACTURER") "Yageo")
        (field (name "MPN") "RC0402JR-070RL")
        (field (name "DIGIKEY_PART_NUMBER_1") "541-1752-1-ND")
        (field (name "MANUFACTURER_1") "Vishay Dale")
        (field (name "MPN_1") "RCG04021M00FKED")
        (field (name "CREATED_BY") "PCBLayout.com")
      )
      (libsource (lib "eagle-import") (part "RC0402JR-070RL"))
    )
    (comp (ref "R11")
      (value "1M")
      (footprint "eagle-import:RES_0402")
      (fields
        (field (name "DIGIKEY_PART_NUMBER") "311-0.0JRTR-ND")
        (field (name "MANUFACTURER") "Yageo")
        (field (name "MPN") "RC0402JR-070RL")
        (field (name "DIGIKEY_PART_NUMBER_1") "13-RE0402BRE071MLCT-ND")
        (field (name "MPN_1") "RE0402BRE071ML")
        (field (name "CREATED_BY") "PCBLayout.com")
      )
      (libsource (lib "eagle-import") (part "RC0402JR-070RL"))
    )
    (comp (ref "R12")
      (value "330R")
      (footprint "eagle-import:RES_0603")
      (fields
        (field (name "DIGIKEY_PART_NUMBER") "311-0.0GRTR-ND")
        (field (name "MANUFACTURER") "Yageo")
        (field (name "MPN") "RC0603JR-070RL")
        (field (name "DIGIKEY_PART_NUMBER_1") "511-1764-1-ND")
        (field (name "MANUFACTURER_1") "Rohm Semiconductor")
        (field (name "MPN_1") "SDR03EZPJ331")
        (field (name "CREATED_BY") "PCBLayout.com")
      )
      (libsource (lib "eagle-import") (part "RC0603JR-070RL"))
    )
    (comp (ref "R13")
      (value "330R")
      (footprint "eagle-import:RES_0603")
      (fields
        (field (name "DIGIKEY_PART_NUMBER") "311-0.0GRTR-ND")
        (field (name "MANUFACTURER") "Yageo")
        (field (name "MPN") "RC0603JR-070RL")
        (field (name "DIGIKEY_PART_NUMBER_1") "511-1764-1-ND")
        (field (name "MANUFACTURER_1") "Rohm Semiconductor")
        (field (name "MPN_1") "SDR03EZPJ331")
        (field (name "CREATED_BY") "PCBLayout.com")
      )
      (libsource (lib "eagle-import") (part "RC0603JR-070RL"))
    )
    (comp (ref "R14")
      (value "330R")
      (footprint "eagle-import:RES_0603")
      (fields
        (field (name "DIGIKEY_PART_NUMBER") "311-0.0GRTR-ND")
        (field (name "MANUFACTURER") "Yageo")
        (field (name "MPN") "RC0603JR-070RL")
        (field (name "DIGIKEY_PART_NUMBER_1") "511-1764-1-ND")
        (field (name "MANUFACTURER_1") "Rohm Semiconductor")
        (field (name "MPN_1") "SDR03EZPJ331")
        (field (name "CREATED_BY") "PCBLayout.com")
      )
      (libsource (lib "eagle-import") (part "RC0603JR-070RL"))
    )
    (comp (ref "R15")
      (value "330R")
      (footprint "eagle-import:RES_0603")
      (fields
        (field (name "DIGIKEY_PART_NUMBER") "311-0.0GRTR-ND")
        (field (name "MANUFACTURER") "Yageo")
        (field (name "MPN") "RC0603JR-070RL")
        (field (name "DIGIKEY_PART_NUMBER_1") "511-1764-1-ND")
        (field (name "MANUFACTURER_1") "Rohm Semiconductor")
        (field (name "MPN_1") "SDR03EZPJ331")
        (field (name "CREATED_BY") "PCBLayout.com")
      )
      (libsource (lib "eagle-import") (part "RC0603JR-070RL"))
    )
    (comp (ref "R16")
      (value "330R")
      (footprint "eagle-import:RES_0603")
      (fields
        (field (name "DIGIKEY_PART_NUMBER") "311-0.0GRTR-ND")
        (field (name "MANUFACTURER") "Yageo")
        (field (name "MPN") "RC0603JR-070RL")
        (field (name "DIGIKEY_PART_NUMBER_1") "511-1764-1-ND")
        (field (name "MANUFACTURER_1") "Rohm Semiconductor")
        (field (name "MPN_1") "SDR03EZPJ331")
        (field (name "CREATED_BY") "PCBLayout.com")
      )
      (libsource (lib "eagle-import") (part "RC0603JR-070RL"))
    )
    (comp (ref "R17")
      (value "330R")
      (footprint "eagle-import:RES_0603")
      (fields
        (field (name "DIGIKEY_PART_NUMBER") "311-0.0GRTR-ND")
        (field (name "MANUFACTURER") "Yageo")
        (field (name "MPN") "RC0603JR-070RL")
        (field (name "DIGIKEY_PART_NUMBER_1") "511-1764-1-ND")
        (field (name "MANUFACTURER_1") "Rohm Semiconductor")
        (field (name "MPN_1") "SDR03EZPJ331")
        (field (name "CREATED_BY") "PCBLayout.com")
      )
      (libsource (lib "eagle-import") (part "RC0603JR-070RL"))
    )
    (comp (ref "R18")
      (value "1M")
      (footprint "eagle-import:RES_0402")
      (fields
        (field (name "DIGIKEY_PART_NUMBER") "311-0.0JRTR-ND")
        (field (name "MANUFACTURER") "Yageo")
        (field (name "MPN") "RC0402JR-070RL")
        (field (name "DIGIKEY_PART_NUMBER_1") "13-RE0402BRE071MLCT-ND")
        (field (name "MPN_1") "RE0402BRE071ML")
        (field (name "CREATED_BY") "PCBLayout.com")
      )
      (libsource (lib "eagle-import") (part "RC0402JR-070RL"))
    )
    (comp (ref "R31")
      (value "90.9K")
      (footprint "eagle-import:RES_0402")
      (fields
        (field (name "DIGIKEY_PART_NUMBER") "311-0.0JRTR-ND")
        (field (name "MANUFACTURER") "Yageo")
        (field (name "MPN") "RC0402JR-070RL")
        (field (name "DIGIKEY_PART_NUMBER_1") "311-2334-1-ND")
        (field (name "MPN_1") "RT0402DRE0790K9L")
        (field (name "CREATED_BY") "PCBLayout.com")
      )
      (libsource (lib "eagle-import") (part "RC0402JR-070RL"))
    )
    (comp (ref "R33")
      (value "10K")
      (footprint "eagle-import:RES_0402")
      (fields
        (field (name "DIGIKEY_PART_NUMBER") "311-0.0JRTR-ND")
        (field (name "MANUFACTURER") "Yageo")
        (field (name "MPN") "RC0402JR-070RL")
        (field (name "DIGIKEY_PART_NUMBER_1") "541-1752-1-ND")
        (field (name "MANUFACTURER_1") "Vishay Dale")
        (field (name "MPN_1") "RCG04021M00FKED")
        (field (name "CREATED_BY") "PCBLayout.com")
      )
      (libsource (lib "eagle-import") (part "RC0402JR-070RL"))
    )
    (comp (ref "Y1")
      (value "40Mhz")
      (footprint "eagle-import:ABM3B-40.000MHZ-B2-T")
      (fields
        (field (name "DIGIKEY_PART_NUMBER") "535-9132-2-ND")
        (field (name "MANUFACTURER") "Abracon LLC")
        (field (name "MPN") "ABM3B-40.000MHZ-B2-T")
        (field (name "CREATED_BY") "PCBLayout.com")
      )
      (libsource (lib "eagle-import") (part "ABM3B-40.000MHZ-B2-T"))
    )
  )
  (nets
    (net (code "1") (name "2.8V") (class "Default")
      (node (ref "C11") (pin "2") (pinfunction "2_2") (pintype "passive"))
      (node (ref "C14") (pin "2") (pinfunction "2_2") (pintype "passive"))
      (node (ref "C15") (pin "2") (pinfunction "2_2") (pintype "passive"))
      (node (ref "C30") (pin "2") (pinfunction "2_2") (pintype "passive"))
      (node (ref "C31") (pin "2") (pinfunction "2_2") (pintype "passive"))
      (node (ref "IC2") (pin "24") (pinfunction "VDD33_3_24") (pintype "power_in"))
      (node (ref "IC2") (pin "51") (pinfunction "VDD33_51") (pintype "power_in"))
      (node (ref "IC2") (pin "7") (pinfunction "VDD33_2_7") (pintype "power_in"))
      (node (ref "L1") (pin "2") (pinfunction "2_2") (pintype "passive"))
      (node (ref "R6") (pin "2") (pinfunction "2_2") (pintype "passive"))
      (node (ref "R7") (pin "2") (pinfunction "2_2") (pintype "passive"))
    )
    (net (code "2") (name "3.3VDDA") (class "Default")
      (node (ref "C32") (pin "2") (pinfunction "2_2") (pintype "passive"))
      (node (ref "C33") (pin "2") (pinfunction "2_2") (pintype "passive"))
      (node (ref "IC2") (pin "34") (pinfunction "VDDA33_2_34") (pintype "power_in"))
      (node (ref "IC2") (pin "40") (pinfunction "VDDA33_3_40") (pintype "power_in"))
      (node (ref "IC2") (pin "48") (pinfunction "VDDA33_4_48") (pintype "power_in"))
      (node (ref "IC2") (pin "62") (pinfunction "VDDA33_62") (pintype "power_in"))
      (node (ref "L3") (pin "2") (pinfunction "2_2") (pintype "passive"))
    )
    (net (code "3") (name "5V") (class "Default")
      (node (ref "C18") (pin "2") (pinfunction "2_2") (pintype "passive"))
      (node (ref "C2") (pin "1") (pinfunction "+_1") (pintype "passive"))
      (node (ref "J1") (pin "P8") (pinfunction "P8_P8") (pintype "passive"))
      (node (ref "J1") (pin "P9") (pinfunction "P9_P9") (pintype "passive"))
      (node (ref "R2") (pin "1") (pinfunction "1_1") (pintype "passive"))
      (node (ref "U7") (pin "8") (pinfunction "OUT2_8") (pintype "output"))
    )
    (net (code "4") (name "12V") (class "Default")
      (node (ref "C12") (pin "1") (pinfunction "+_1") (pintype "passive"))
      (node (ref "C13") (pin "1") (pinfunction "1_1") (pintype "passive"))
      (node (ref "F1") (pin "2") (pinfunction "2_2") (pintype "passive"))
      (node (ref "J2") (pin "PWR") (pinfunction "PWR_PWR") (pintype "bidirectional"))
    )
    (net (code "5") (name "AGND") (class "Default")
      (node (ref "C20") (pin "1") (pinfunction "1_1") (pintype "passive"))
      (node (ref "IC7") (pin "12") (pinfunction "AGND_12") (pintype "power_in"))
      (node (ref "IC7") (pin "21") (pinfunction "EPAD_21") (pintype "passive"))
      (node (ref "IC7") (pin "9") (pinfunction "MODE_9") (pintype "input"))
      (node (ref "R26") (pin "1") (pinfunction "1_1") (pintype "passive"))
    )
    (net (code "6") (name "BOARD_1.8V") (class "Default")
      (node (ref "C24") (pin "2") (pinfunction "2_2") (pintype "passive"))
      (node (ref "IC7") (pin "16") (pinfunction "FB_LDO2_16") (pintype "input"))
      (node (ref "IC7") (pin "17") (pinfunction "VLDO2_17") (pintype "output"))
    )
    (net (code "7") (name "BOARD_5V") (class "Default")
      (node (ref "C17") (pin "2") (pinfunction "2_2") (pintype "passive"))
      (node (ref "C19") (pin "2") (pinfunction "2_2") (pintype "passive"))
      (node (ref "IC7") (pin "10") (pinfunction "EN_DCDC_10") (pintype "input"))
      (node (ref "IC7") (pin "15") (pinfunction "VINLDO1_15") (pintype "input"))
      (node (ref "IC7") (pin "18") (pinfunction "VINLDO2_18") (pintype "input"))
      (node (ref "IC7") (pin "19") (pinfunction "RSTSNS_19") (pintype "input"))
      (node (ref "IC7") (pin "3") (pinfunction "EN_LDO1_3") (pintype "input"))
      (node (ref "IC7") (pin "4") (pinfunction "EN_LDO2_4") (pintype "input"))
      (node (ref "IC7") (pin "8") (pinfunction "VINDCDC_8") (pintype "input"))
      (node (ref "R21") (pin "1") (pinfunction "1_1") (pintype "passive"))
      (node (ref "U7") (pin "9") (pinfunction "OUT1_9") (pintype "output"))
    )
    (net (code "8") (name "B_3.3V") (class "Default")
      (node (ref "C23") (pin "2") (pinfunction "2_2") (pintype "passive"))
      (node (ref "C46") (pin "2") (pinfunction "2_2") (pintype "passive"))
      (node (ref "IC1") (pin "8") (pinfunction "VCC_8") (pintype "passive"))
      (node (ref "IC7") (pin "13") (pinfunction "FB_LDO1_13") (pintype "input"))
      (node (ref "IC7") (pin "14") (pinfunction "VLDO1_14") (pintype "output"))
      (node (ref "J1") (pin "P1") (pinfunction "P1_P1") (pintype "passive"))
      (node (ref "J1") (pin "P2") (pinfunction "P2_P2") (pintype "passive"))
      (node (ref "L1") (pin "1") (pinfunction "1_1") (pintype "passive"))
      (node (ref "L3") (pin "1") (pinfunction "1_1") (pintype "passive"))
      (node (ref "R1") (pin "1") (pinfunction "1_1") (pintype "passive"))
      (node (ref "R12") (pin "2") (pinfunction "2_2") (pintype "passive"))
      (node (ref "R13") (pin "2") (pinfunction "2_2") (pintype "passive"))
      (node (ref "R14") (pin "2") (pinfunction "2_2") (pintype "passive"))
      (node (ref "R15") (pin "2") (pinfunction "2_2") (pintype "passive"))
      (node (ref "R16") (pin "2") (pinfunction "2_2") (pintype "passive"))
      (node (ref "R17") (pin "2") (pinfunction "2_2") (pintype "passive"))
      (node (ref "R20") (pin "2") (pinfunction "2_2") (pintype "passive"))
      (node (ref "R22") (pin "2") (pinfunction "2_2") (pintype "passive"))
      (node (ref "R23") (pin "2") (pinfunction "2_2") (pintype "passive"))
      (node (ref "R4") (pin "2") (pinfunction "2_2") (pintype "passive"))
      (node (ref "R5") (pin "2") (pinfunction "2_2") (pintype "passive"))
      (node (ref "R8") (pin "2") (pinfunction "2_2") (pintype "passive"))
      (node (ref "R9") (pin "2") (pinfunction "2_2") (pintype "passive"))
    )
    (net (code "9") (name "CAP_SATARX_N") (class "Default")
      (node (ref "C4") (pin "2") (pinfunction "2_2") (pintype "passive"))
      (node (ref "J1") (pin "S5") (pinfunction "S5_S5") (pintype "passive"))
    )
    (net (code "10") (name "CAP_SATARX_P") (class "Default")
      (node (ref "C7") (pin "2") (pinfunction "2_2") (pintype "passive"))
      (node (ref "J1") (pin "S6") (pinfunction "S6_S6") (pintype "passive"))
    )
    (net (code "11") (name "CAP_SATATX_N") (class "Default")
      (node (ref "C6") (pin "2") (pinfunction "2_2") (pintype "passive"))
      (node (ref "J1") (pin "S2") (pinfunction "S2_S2") (pintype "passive"))
    )
    (net (code "12") (name "CAP_SATATX_P") (class "Default")
      (node (ref "C5") (pin "2") (pinfunction "2_2") (pintype "passive"))
      (node (ref "J1") (pin "S3") (pinfunction "S3_S3") (pintype "passive"))
    )
    (net (code "13") (name "CAP_SSTX_N") (class "Default")
      (node (ref "C26") (pin "1") (pinfunction "1_1") (pintype "passive"))
      (node (ref "IC4") (pin "1") (pinfunction "D+_1") (pintype "passive"))
      (node (ref "J3") (pin "8") (pinfunction "STDA_SSTX-_8") (pintype "bidirectional"))
    )
    (net (code "14") (name "CAP_SSTX_P") (class "Default")
      (node (ref "C28") (pin "1") (pinfunction "1_1") (pintype "passive"))
      (node (ref "IC4") (pin "2") (pinfunction "D-_2") (pintype "passive"))
      (node (ref "J3") (pin "9") (pinfunction "STDA_SSTX+_9") (pintype "bidirectional"))
    )
    (net (code "15") (name "FAULT#") (class "Default")
      (node (ref "IC2") (pin "23") (pinfunction "SPI_CS2/GPIO11_23") (pintype "bidirectional"))
      (node (ref "R20") (pin "1") (pinfunction "1_1") (pintype "passive"))
      (node (ref "U7") (pin "10") (pinfunction "~{FAULT1}_10") (pintype "output"))
      (node (ref "U7") (pin "6") (pinfunction "~{FAULT2}_6") (pintype "output"))
    )
    (net (code "16") (name "FUSE_12V") (class "Default")
      (node (ref "C1") (pin "1") (pinfunction "+_1") (pintype "passive"))
      (node (ref "F1") (pin "1") (pinfunction "1_1") (pintype "passive"))
      (node (ref "J1") (pin "P14") (pinfunction "P14_P14") (pintype "passive"))
      (node (ref "J1") (pin "P15") (pinfunction "P15_P15") (pintype "passive"))
      (node (ref "R3") (pin "1") (pinfunction "1_1") (pintype "passive"))
    )
    (net (code "17") (name "GND") (class "Default")
      (node (ref "C1") (pin "2") (pinfunction "-_2") (pintype "passive"))
      (node (ref "C10") (pin "2") (pinfunction "2_2") (pintype "passive"))
      (node (ref "C11") (pin "1") (pinfunction "1_1") (pintype "passive"))
      (node (ref "C12") (pin "2") (pinfunction "-_2") (pintype "passive"))
      (node (ref "C13") (pin "2") (pinfunction "2_2") (pintype "passive"))
      (node (ref "C14") (pin "1") (pinfunction "1_1") (pintype "passive"))
      (node (ref "C15") (pin "1") (pinfunction "1_1") (pintype "passive"))
      (node (ref "C16") (pin "1") (pinfunction "1_1") (pintype "passive"))
      (node (ref "C17") (pin "1") (pinfunction "1_1") (pintype "passive"))
      (node (ref "C18") (pin "1") (pinfunction "1_1") (pintype "passive"))
      (node (ref "C19") (pin "1") (pinfunction "1_1") (pintype "passive"))
      (node (ref "C2") (pin "2") (pinfunction "-_2") (pintype "passive"))
      (node (ref "C21") (pin "1") (pinfunction "1_1") (pintype "passive"))
      (node (ref "C23") (pin "1") (pinfunction "1_1") (pintype "passive"))
      (node (ref "C24") (pin "1") (pinfunction "1_1") (pintype "passive"))
      (node (ref "C25") (pin "1") (pinfunction "1_1") (pintype "passive"))
      (node (ref "C27") (pin "2") (pinfunction "2_2") (pintype "passive"))
      (node (ref "C3") (pin "1") (pinfunction "1_1") (pintype "passive"))
      (node (ref "C30") (pin "1") (pinfunction "1_1") (pintype "passive"))
      (node (ref "C31") (pin "1") (pinfunction "1_1") (pintype "passive"))
      (node (ref "C32") (pin "1") (pinfunction "1_1") (pintype "passive"))
      (node (ref "C33") (pin "1") (pinfunction "1_1") (pintype "passive"))
      (node (ref "C34") (pin "1") (pinfunction "1_1") (pintype "passive"))
      (node (ref "C35") (pin "1") (pinfunction "1_1") (pintype "passive"))
      (node (ref "C36") (pin "1") (pinfunction "1_1") (pintype "passive"))
      (node (ref "C37") (pin "1") (pinfunction "1_1") (pintype "passive"))
      (node (ref "C38") (pin "1") (pinfunction "1_1") (pintype "passive"))
      (node (ref "C39") (pin "2") (pinfunction "2_2") (pintype "passive"))
      (node (ref "C40") (pin "1") (pinfunction "1_1") (pintype "passive"))
      (node (ref "C41") (pin "1") (pinfunction "1_1") (pintype "passive"))
      (node (ref "C42") (pin "1") (pinfunction "1_1") (pintype "passive"))
      (node (ref "C43") (pin "2") (pinfunction "2_2") (pintype "passive"))
      (node (ref "C44") (pin "1") (pinfunction "1_1") (pintype "passive"))
      (node (ref "C45") (pin "1") (pinfunction "1_1") (pintype "passive"))
      (node (ref "C46") (pin "1") (pinfunction "1_1") (pintype "passive"))
      (node (ref "C8") (pin "1") (pinfunction "1_1") (pintype "passive"))
      (node (ref "C9") (pin "2") (pinfunction "2_2") (pintype "passive"))
      (node (ref "IC1") (pin "4") (pinfunction "GND_4") (pintype "passive"))
      (node (ref "IC2") (pin "29") (pinfunction "JTAG_TRSTZ_29") (pintype "input"))
      (node (ref "IC2") (pin "44") (pinfunction "VSS_2_44") (pintype "power_in"))
      (node (ref "IC2") (pin "53") (pinfunction "VSSOSC_53") (pintype "power_in"))
      (node (ref "IC2") (pin "58") (pinfunction "VSS_58") (pintype "power_in"))
      (node (ref "IC2") (pin "EPAD") (pinfunction "EPAD_EPAD") (pintype "passive"))
      (node (ref "IC3") (pin "3") (pinfunction "GND_3") (pintype "power_in"))
      (node (ref "IC4") (pin "3") (pinfunction "GND_3") (pintype "power_in"))
      (node (ref "IC5") (pin "3") (pinfunction "GND_3") (pintype "power_in"))
      (node (ref "IC7") (pin "6") (pinfunction "PGND_6") (pintype "power_in"))
      (node (ref "J1") (pin "P10") (pinfunction "P10_P10") (pintype "passive"))
      (node (ref "J1") (pin "P12") (pinfunction "P12_P12") (pintype "passive"))
      (node (ref "J1") (pin "P4") (pinfunction "P4_P4") (pintype "passive"))
      (node (ref "J1") (pin "P5") (pinfunction "P5_P5") (pintype "passive"))
      (node (ref "J1") (pin "P6") (pinfunction "P6_P6") (pintype "passive"))
      (node (ref "J1") (pin "S1") (pinfunction "S1_S1") (pintype "passive"))
      (node (ref "J1") (pin "S4") (pinfunction "S4_S4") (pintype "passive"))
      (node (ref "J1") (pin "S7") (pinfunction "S7_S7") (pintype "passive"))
      (node (ref "J2") (pin "GND") (pinfunction "GND_GND") (pintype "bidirectional"))
      (node (ref "J2") (pin "GNDBREAK") (pinfunction "GNDBREAK_GNDBREAK") (pintype "bidirectional"))
      (node (ref "J3") (pin "4") (pinfunction "GND_4") (pintype "bidirectional"))
      (node (ref "J3") (pin "7") (pinfunction "GND_DRAIN_7") (pintype "bidirectional"))
      (node (ref "R18") (pin "1") (pinfunction "1_1") (pintype "passive"))
      (node (ref "R19") (pin "2") (pinfunction "2_2") (pintype "passive"))
      (node (ref "R25") (pin "1") (pinfunction "1_1") (pintype "passive"))
      (node (ref "R26") (pin "2") (pinfunction "2_2") (pintype "passive"))
      (node (ref "R29") (pin "2") (pinfunction "2_2") (pintype "passive"))
      (node (ref "R33") (pin "1") (pinfunction "1_1") (pintype "passive"))
      (node (ref "SW1") (pin "1") (pinfunction "1_1") (pintype "passive"))
      (node (ref "U7") (pin "1") (pinfunction "GND_1") (pintype "power_in"))
      (node (ref "U7") (pin "4") (pinfunction "EN1_4") (pintype "input"))
      (node (ref "Y1") (pin "2") (pinfunction "2_2") (pintype "passive"))
      (node (ref "Y1") (pin "4") (pinfunction "4_4") (pintype "passive"))
    )
    (net (code "18") (name "GRST#") (class "Default")
      (node (ref "IC2") (pin "4") (pinfunction "GRSTZ_4") (pintype "input"))
      (node (ref "IC7") (pin "20") (pinfunction "~{RST}_20") (pintype "output"))
      (node (ref "R23") (pin "1") (pinfunction "1_1") (pintype "passive"))
    )
    (net (code "19") (name "HDD_ACT#") (class "Default")
      (node (ref "D1") (pin "C") (pinfunction "C_C") (pintype "passive"))
      (node (ref "IC2") (pin "2") (pinfunction "PWM0_2") (pintype "output"))
    )
    (net (code "20") (name "HS_FS_CONNECT#") (class "Default")
      (node (ref "D4") (pin "C") (pinfunction "C_C") (pintype "passive"))
      (node (ref "IC2") (pin "15") (pinfunction "GPIO6_15") (pintype "bidirectional"))
    )
    (net (code "21") (name "HS_FS_SUSPEND#") (class "Default")
      (node (ref "D3") (pin "C") (pinfunction "C_C") (pintype "passive"))
      (node (ref "IC2") (pin "10") (pinfunction "GPIO2_10") (pintype "bidirectional"))
    )
    (net (code "22") (name "MISC_LED0#") (class "Default")
      (node (ref "D2") (pin "C") (pinfunction "C_C") (pintype "passive"))
      (node (ref "IC2") (pin "3") (pinfunction "PWM1_3") (pintype "output"))
    )
    (net (code "23") (name "Net-(C27-Pad1)") (class "Default")
      (node (ref "C27") (pin "1") (pinfunction "1_1") (pintype "passive"))
      (node (ref "C8") (pin "2") (pinfunction "2_2") (pintype "passive"))
      (node (ref "J3") (pin "S1") (pinfunction "SHIELD_S1") (pintype "bidirectional"))
      (node (ref "J3") (pin "S2") (pinfunction "SHIELD_S2") (pintype "bidirectional"))
      (node (ref "R18") (pin "2") (pinfunction "2_2") (pintype "passive"))
    )
    (net (code "24") (name "Net-(D1-PadA)") (class "Default")
      (node (ref "D1") (pin "A") (pinfunction "A_A") (pintype "passive"))
      (node (ref "R12") (pin "1") (pinfunction "1_1") (pintype "passive"))
    )
    (net (code "25") (name "Net-(D2-PadA)") (class "Default")
      (node (ref "D2") (pin "A") (pinfunction "A_A") (pintype "passive"))
      (node (ref "R8") (pin "1") (pinfunction "1_1") (pintype "passive"))
    )
    (net (code "26") (name "Net-(D3-PadA)") (class "Default")
      (node (ref "D3") (pin "A") (pinfunction "A_A") (pintype "passive"))
      (node (ref "R9") (pin "1") (pinfunction "1_1") (pintype "passive"))
    )
    (net (code "27") (name "Net-(D4-PadA)") (class "Default")
      (node (ref "D4") (pin "A") (pinfunction "A_A") (pintype "passive"))
      (node (ref "R13") (pin "1") (pinfunction "1_1") (pintype "passive"))
    )
    (net (code "28") (name "Net-(D5-PadA)") (class "Default")
      (node (ref "D5") (pin "A") (pinfunction "A_A") (pintype "passive"))
      (node (ref "R14") (pin "1") (pinfunction "1_1") (pintype "passive"))
    )
    (net (code "29") (name "Net-(D6-PadA)") (class "Default")
      (node (ref "D6") (pin "A") (pinfunction "A_A") (pintype "passive"))
      (node (ref "R15") (pin "1") (pinfunction "1_1") (pintype "passive"))
    )
    (net (code "30") (name "Net-(D7-PadA)") (class "Default")
      (node (ref "D7") (pin "A") (pinfunction "A_A") (pintype "passive"))
      (node (ref "R16") (pin "1") (pinfunction "1_1") (pintype "passive"))
    )
    (net (code "31") (name "Net-(D8-PadA)") (class "Default")
      (node (ref "D8") (pin "A") (pinfunction "A_A") (pintype "passive"))
      (node (ref "R17") (pin "1") (pinfunction "1_1") (pintype "passive"))
    )
    (net (code "32") (name "Net-(IC1-HOLD#)") (class "Default")
      (node (ref "C3") (pin "2") (pinfunction "2_2") (pintype "passive"))
      (node (ref "IC1") (pin "7") (pinfunction "HOLD#_7") (pintype "input"))
      (node (ref "R4") (pin "1") (pinfunction "1_1") (pintype "passive"))
    )
    (net (code "33") (name "Net-(IC1-SO)") (class "Default")
      (node (ref "IC1") (pin "2") (pinfunction "SO_2") (pintype "input"))
      (node (ref "JP1") (pin "2") (pinfunction "2_2") (pintype "passive"))
    )
    (net (code "34") (name "Net-(IC1-WP#)") (class "Default")
      (node (ref "IC1") (pin "3") (pinfunction "WP#_3") (pintype "output"))
      (node (ref "R5") (pin "1") (pinfunction "1_1") (pintype "passive"))
    )
    (net (code "35") (name "Net-(IC2-FREQSEL0)") (class "Default")
      (node (ref "IC2") (pin "30") (pinfunction "FREQSEL0_30") (pintype "input"))
      (node (ref "R6") (pin "1") (pinfunction "1_1") (pintype "passive"))
    )
    (net (code "36") (name "Net-(IC2-FREQSEL1)") (class "Default")
      (node (ref "IC2") (pin "31") (pinfunction "FREQSEL1_31") (pintype "input"))
      (node (ref "R7") (pin "1") (pinfunction "1_1") (pintype "passive"))
    )
    (net (code "37") (name "Net-(IC2-USB_R1)") (class "Default")
      (node (ref "IC2") (pin "38") (pinfunction "USB_R1_38") (pintype "output"))
      (node (ref "R10") (pin "2") (pinfunction "2_2") (pintype "passive"))
    )
    (net (code "38") (name "Net-(IC2-USB_R1RTN)") (class "Default")
      (node (ref "IC2") (pin "39") (pinfunction "USB_R1RTN_39") (pintype "input"))
      (node (ref "R10") (pin "1") (pinfunction "1_1") (pintype "passive"))
    )
    (net (code "39") (name "Net-(IC2-USB_VBUS)") (class "Default")
      (node (ref "IC2") (pin "50") (pinfunction "USB_VBUS_50") (pintype "input"))
      (node (ref "R31") (pin "1") (pinfunction "1_1") (pintype "passive"))
      (node (ref "R33") (pin "2") (pinfunction "2_2") (pintype "passive"))
    )
    (net (code "40") (name "Net-(IC2-XI)") (class "Default")
      (node (ref "C10") (pin "1") (pinfunction "1_1") (pintype "passive"))
      (node (ref "IC2") (pin "52") (pinfunction "XI_52") (pintype "input"))
      (node (ref "R11") (pin "1") (pinfunction "1_1") (pintype "passive"))
      (node (ref "Y1") (pin "1") (pinfunction "1_1") (pintype "passive"))
    )
    (net (code "41") (name "Net-(IC2-XO)") (class "Default")
      (node (ref "C9") (pin "1") (pinfunction "1_1") (pintype "passive"))
      (node (ref "IC2") (pin "54") (pinfunction "XO_54") (pintype "output"))
      (node (ref "R11") (pin "2") (pinfunction "2_2") (pintype "passive"))
      (node (ref "Y1") (pin "3") (pinfunction "3_3") (pintype "passive"))
    )
    (net (code "42") (name "Net-(IC7-FB_DCDC)") (class "Default")
      (node (ref "C22") (pin "1") (pinfunction "1_1") (pintype "passive"))
      (node (ref "IC7") (pin "11") (pinfunction "FB_DCDC_11") (pintype "input"))
      (node (ref "R28") (pin "1") (pinfunction "1_1") (pintype "passive"))
      (node (ref "R29") (pin "1") (pinfunction "1_1") (pintype "passive"))
    )
    (net (code "43") (name "Net-(IC7-SW)") (class "Default")
      (node (ref "IC7") (pin "7") (pinfunction "SW_7") (pintype "output"))
      (node (ref "L2") (pin "2") (pinfunction "2_2") (pintype "passive"))
    )
    (net (code "44") (name "Net-(IC7-TRST)") (class "Default")
      (node (ref "C20") (pin "2") (pinfunction "2_2") (pintype "passive"))
      (node (ref "IC7") (pin "2") (pinfunction "TRST_2") (pintype "bidirectional"))
    )
    (net (code "45") (name "Net-(IC7-~{MR})") (class "Default")
      (node (ref "IC7") (pin "1") (pinfunction "~{MR}_1") (pintype "input"))
      (node (ref "R21") (pin "2") (pinfunction "2_2") (pintype "passive"))
      (node (ref "SW1") (pin "2") (pinfunction "2_2") (pintype "passive"))
    )
    (net (code "46") (name "Net-(J1-PadP3)") (class "Default")
      (node (ref "J1") (pin "P3") (pinfunction "P3_P3") (pintype "passive"))
      (node (ref "R1") (pin "2") (pinfunction "2_2") (pintype "passive"))
    )
    (net (code "47") (name "Net-(J1-PadP7)") (class "Default")
      (node (ref "J1") (pin "P7") (pinfunction "P7_P7") (pintype "passive"))
      (node (ref "R2") (pin "2") (pinfunction "2_2") (pintype "passive"))
    )
    (net (code "48") (name "Net-(J1-PadP13)") (class "Default")
      (node (ref "J1") (pin "P13") (pinfunction "P13_P13") (pintype "passive"))
      (node (ref "R3") (pin "2") (pinfunction "2_2") (pintype "passive"))
    )
    (net (code "49") (name "Net-(U7-ILIM)") (class "Default")
      (node (ref "R25") (pin "2") (pinfunction "2_2") (pintype "passive"))
      (node (ref "U7") (pin "7") (pinfunction "ILIM_7") (pintype "output"))
    )
    (net (code "50") (name "PBUTTON#") (class "Default")
      (node (ref "IC2") (pin "11") (pinfunction "GPIO3_11") (pintype "bidirectional"))
    )
    (net (code "51") (name "PWR_STATE_0") (class "Default")
      (node (ref "D7") (pin "C") (pinfunction "C_C") (pintype "passive"))
      (node (ref "IC2") (pin "9") (pinfunction "GPIO1_9") (pintype "bidirectional"))
    )
    (net (code "52") (name "PWR_STATE_1") (class "Default")
      (node (ref "D8") (pin "C") (pinfunction "C_C") (pintype "passive"))
      (node (ref "IC2") (pin "14") (pinfunction "GPIO5_14") (pintype "bidirectional"))
    )
    (net (code "53") (name "SATARX_N") (class "Default")
      (node (ref "C4") (pin "1") (pinfunction "1_1") (pintype "passive"))
      (node (ref "IC2") (pin "59") (pinfunction "SATA_RXM_59") (pintype "input"))
    )
    (net (code "54") (name "SATARX_P") (class "Default")
      (node (ref "C7") (pin "1") (pinfunction "1_1") (pintype "passive"))
      (node (ref "IC2") (pin "60") (pinfunction "SATA_RXP_60") (pintype "input"))
    )
    (net (code "55") (name "SATATX_N") (class "Default")
      (node (ref "C6") (pin "1") (pinfunction "1_1") (pintype "passive"))
      (node (ref "IC2") (pin "56") (pinfunction "SATA_TXM_56") (pintype "output"))
    )
    (net (code "56") (name "SATATX_P") (class "Default")
      (node (ref "C5") (pin "1") (pinfunction "1_1") (pintype "passive"))
      (node (ref "IC2") (pin "57") (pinfunction "SATA_TXP_57") (pintype "output"))
    )
    (net (code "57") (name "SATA_EN") (class "Default")
      (node (ref "IC2") (pin "22") (pinfunction "SPI_CS1/GPIO10_22") (pintype "bidirectional"))
      (node (ref "R19") (pin "1") (pinfunction "1_1") (pintype "passive"))
      (node (ref "R22") (pin "1") (pinfunction "1_1") (pintype "passive"))
      (node (ref "U7") (pin "5") (pinfunction "EN2_5") (pintype "input"))
    )
    (net (code "58") (name "SELF_PWR") (class "Default")
      (node (ref "IC2") (pin "13") (pinfunction "GPIO4_13") (pintype "bidirectional"))
    )
    (net (code "59") (name "SPI_CE#") (class "Default")
      (node (ref "IC1") (pin "1") (pinfunction "CE#_1") (pintype "input"))
      (node (ref "IC2") (pin "21") (pinfunction "SPI_CS0_21") (pintype "output"))
    )
    (net (code "60") (name "SPI_SCK") (class "Default")
      (node (ref "IC1") (pin "6") (pinfunction "SCK_6") (pintype "passive"))
      (node (ref "IC2") (pin "17") (pinfunction "SPI_SCLK_17") (pintype "output"))
    )
    (net (code "61") (name "SPI_SI") (class "Default")
      (node (ref "IC2") (pin "20") (pinfunction "SPI_DATA_IN_20") (pintype "input"))
      (node (ref "JP1") (pin "1") (pinfunction "1_1") (pintype "passive"))
    )
    (net (code "62") (name "SPI_SO") (class "Default")
      (node (ref "IC1") (pin "5") (pinfunction "SI_5") (pintype "passive"))
      (node (ref "IC2") (pin "18") (pinfunction "SPI_DATA_OUT_18") (pintype "output"))
    )
    (net (code "63") (name "SSRX_N") (class "Default")
      (node (ref "IC2") (pin "45") (pinfunction "USB_SSRXM_45") (pintype "input"))
      (node (ref "IC5") (pin "1") (pinfunction "D+_1") (pintype "passive"))
      (node (ref "J3") (pin "5") (pinfunction "STDA_SSRX-_5") (pintype "bidirectional"))
    )
    (net (code "64") (name "SSRX_P") (class "Default")
      (node (ref "IC2") (pin "46") (pinfunction "USB_SSRXP_46") (pintype "input"))
      (node (ref "IC5") (pin "2") (pinfunction "D-_2") (pintype "passive"))
      (node (ref "J3") (pin "6") (pinfunction "STDA_SSRX+_6") (pintype "bidirectional"))
    )
    (net (code "65") (name "SSTX_N") (class "Default")
      (node (ref "C26") (pin "2") (pinfunction "2_2") (pintype "passive"))
      (node (ref "IC2") (pin "42") (pinfunction "USB_SSTXM_42") (pintype "output"))
    )
    (net (code "66") (name "SSTX_P") (class "Default")
      (node (ref "C28") (pin "2") (pinfunction "2_2") (pintype "passive"))
      (node (ref "IC2") (pin "43") (pinfunction "USB_SSTXP_43") (pintype "output"))
    )
    (net (code "67") (name "SS_CONNECT#") (class "Default")
      (node (ref "D5") (pin "C") (pinfunction "C_C") (pintype "passive"))
      (node (ref "IC2") (pin "16") (pinfunction "GPIO7_16") (pintype "bidirectional"))
    )
    (net (code "68") (name "SW_HB") (class "Default")
      (node (ref "D6") (pin "C") (pinfunction "C_C") (pintype "passive"))
      (node (ref "IC2") (pin "8") (pinfunction "GPIO0_8") (pintype "bidirectional"))
    )
    (net (code "69") (name "USB_D_N") (class "Default")
      (node (ref "IC2") (pin "35") (pinfunction "USB_DM_35") (pintype "bidirectional"))
      (node (ref "IC3") (pin "1") (pinfunction "D+_1") (pintype "passive"))
      (node (ref "J3") (pin "2") (pinfunction "D-_2") (pintype "bidirectional"))
    )
    (net (code "70") (name "USB_D_P") (class "Default")
      (node (ref "IC2") (pin "36") (pinfunction "USB_DP_36") (pintype "bidirectional"))
      (node (ref "IC3") (pin "2") (pinfunction "D-_2") (pintype "passive"))
      (node (ref "J3") (pin "3") (pinfunction "D+_3") (pintype "bidirectional"))
    )
    (net (code "71") (name "VDD_1.1V") (class "Default")
      (node (ref "C21") (pin "2") (pinfunction "2_2") (pintype "passive"))
      (node (ref "C22") (pin "2") (pinfunction "2_2") (pintype "passive"))
      (node (ref "C34") (pin "2") (pinfunction "2_2") (pintype "passive"))
      (node (ref "C35") (pin "2") (pinfunction "2_2") (pintype "passive"))
      (node (ref "C36") (pin "2") (pinfunction "2_2") (pintype "passive"))
      (node (ref "C37") (pin "2") (pinfunction "2_2") (pintype "passive"))
      (node (ref "C38") (pin "2") (pinfunction "2_2") (pintype "passive"))
      (node (ref "C39") (pin "1") (pinfunction "1_1") (pintype "passive"))
      (node (ref "C40") (pin "2") (pinfunction "2_2") (pintype "passive"))
      (node (ref "C41") (pin "2") (pinfunction "2_2") (pintype "passive"))
      (node (ref "C42") (pin "2") (pinfunction "2_2") (pintype "passive"))
      (node (ref "C43") (pin "1") (pinfunction "1_1") (pintype "passive"))
      (node (ref "C44") (pin "2") (pinfunction "2_2") (pintype "passive"))
      (node (ref "C45") (pin "2") (pinfunction "2_2") (pintype "passive"))
      (node (ref "IC2") (pin "1") (pinfunction "VDD_2_1") (pintype "power_in"))
      (node (ref "IC2") (pin "12") (pinfunction "VDD_3_12") (pintype "power_in"))
      (node (ref "IC2") (pin "19") (pinfunction "VDD_4_19") (pintype "power_in"))
      (node (ref "IC2") (pin "32") (pinfunction "VDD_5_32") (pintype "power_in"))
      (node (ref "IC2") (pin "33") (pinfunction "VDD_6_33") (pintype "power_in"))
      (node (ref "IC2") (pin "41") (pinfunction "VDD_7_41") (pintype "power_in"))
      (node (ref "IC2") (pin "47") (pinfunction "VDD_8_47") (pintype "power_in"))
      (node (ref "IC2") (pin "49") (pinfunction "VDD_9_49") (pintype "power_in"))
      (node (ref "IC2") (pin "55") (pinfunction "VDD_10_55") (pintype "power_in"))
      (node (ref "IC2") (pin "61") (pinfunction "VDD_11_61") (pintype "power_in"))
      (node (ref "IC2") (pin "63") (pinfunction "VDD_63") (pintype "power_in"))
      (node (ref "L2") (pin "1") (pinfunction "1_1") (pintype "passive"))
      (node (ref "R28") (pin "2") (pinfunction "2_2") (pintype "passive"))
    )
    (net (code "72") (name "VIN") (class "Default")
      (node (ref "C16") (pin "2") (pinfunction "2_2") (pintype "passive"))
      (node (ref "C25") (pin "2") (pinfunction "2_2") (pintype "passive"))
      (node (ref "J3") (pin "1") (pinfunction "VBUS_1") (pintype "bidirectional"))
      (node (ref "R31") (pin "2") (pinfunction "2_2") (pintype "passive"))
      (node (ref "U7") (pin "2") (pinfunction "IN_2_2") (pintype "input"))
      (node (ref "U7") (pin "3") (pinfunction "IN_3") (pintype "input"))
    )
    (net (code "73") (name "unconnected-(IC2-GPIO8{slash}UART_RX-Pad5)") (class "Default")
      (node (ref "IC2") (pin "5") (pinfunction "GPIO8/UART_RX_5") (pintype "bidirectional"))
    )
    (net (code "74") (name "unconnected-(IC2-GPIO9{slash}UART_TX-Pad6)") (class "Default")
      (node (ref "IC2") (pin "6") (pinfunction "GPIO9/UART_TX_6") (pintype "bidirectional"))
    )
    (net (code "75") (name "unconnected-(IC2-JTAG_TCK-Pad25)") (class "Default")
      (node (ref "IC2") (pin "25") (pinfunction "JTAG_TCK_25") (pintype "input"))
    )
    (net (code "76") (name "unconnected-(IC2-JTAG_TDI-Pad26)") (class "Default")
      (node (ref "IC2") (pin "26") (pinfunction "JTAG_TDI_26") (pintype "input"))
    )
    (net (code "77") (name "unconnected-(IC2-JTAG_TDO-Pad27)") (class "Default")
      (node (ref "IC2") (pin "27") (pinfunction "JTAG_TDO_27") (pintype "output"))
    )
    (net (code "78") (name "unconnected-(IC2-JTAG_TMS-Pad28)") (class "Default")
      (node (ref "IC2") (pin "28") (pinfunction "JTAG_TMS_28") (pintype "input"))
    )
    (net (code "79") (name "unconnected-(IC2-NC-Pad64)") (class "Default")
      (node (ref "IC2") (pin "64") (pinfunction "NC_64") (pintype "passive"))
    )
    (net (code "80") (name "unconnected-(IC2-NC_2-Pad37)") (class "Default")
      (node (ref "IC2") (pin "37") (pinfunction "NC_2_37") (pintype "passive"))
    )
    (net (code "81") (name "unconnected-(IC7-~{PG}-Pad5)") (class "Default")
      (node (ref "IC7") (pin "5") (pinfunction "~{PG}_5") (pintype "output"))
    )
    (net (code "82") (name "unconnected-(J1-PadP11)") (class "Default")
      (node (ref "J1") (pin "P11") (pinfunction "P11_P11") (pintype "passive"))
    )
  )
)
